# UPCNSL-ABS-FLS-ARD_v1_2.net
KiCad netlist of a schematic drawn in Altium Designer
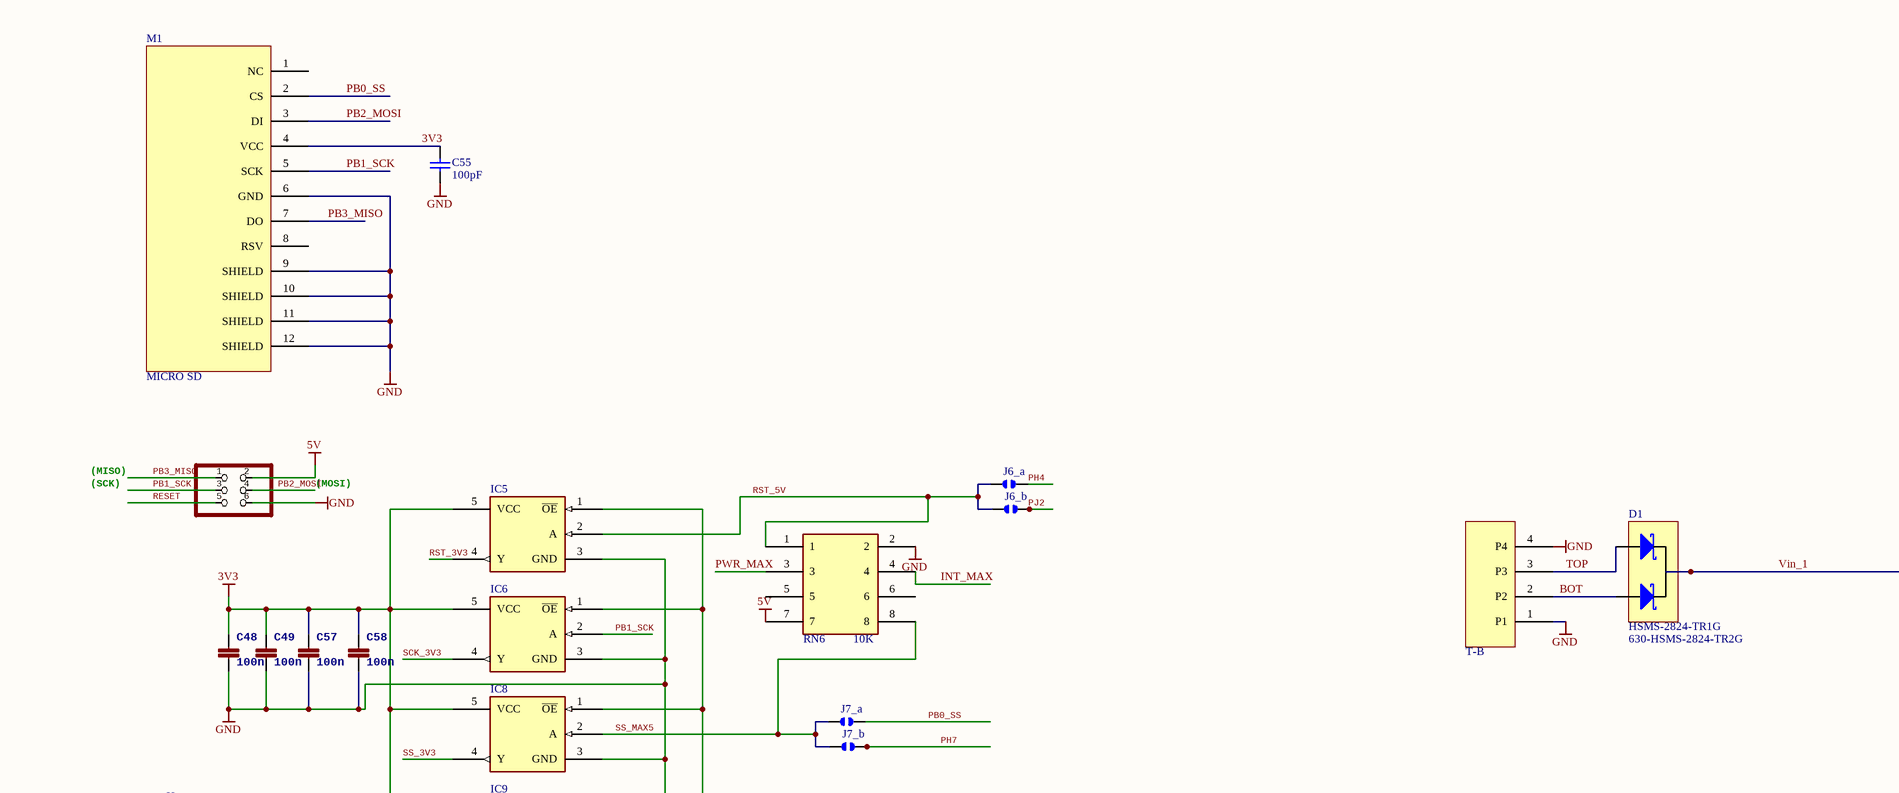
[diagram p0: UPCNSL-ABS-FLS-ARD_v1.2.SchDoc, top left]
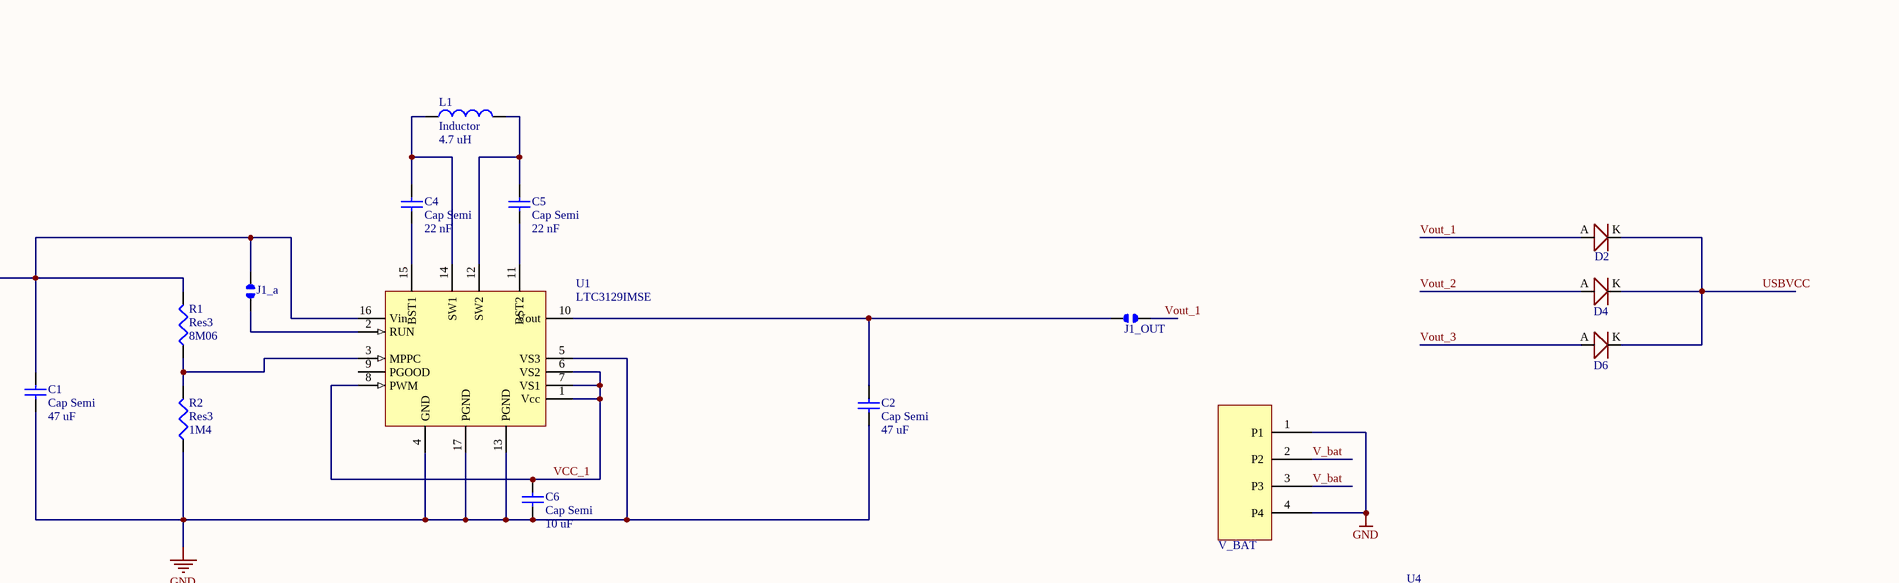
[diagram p1: UPCNSL-ABS-FLS-ARD_v1.2.SchDoc, top right]
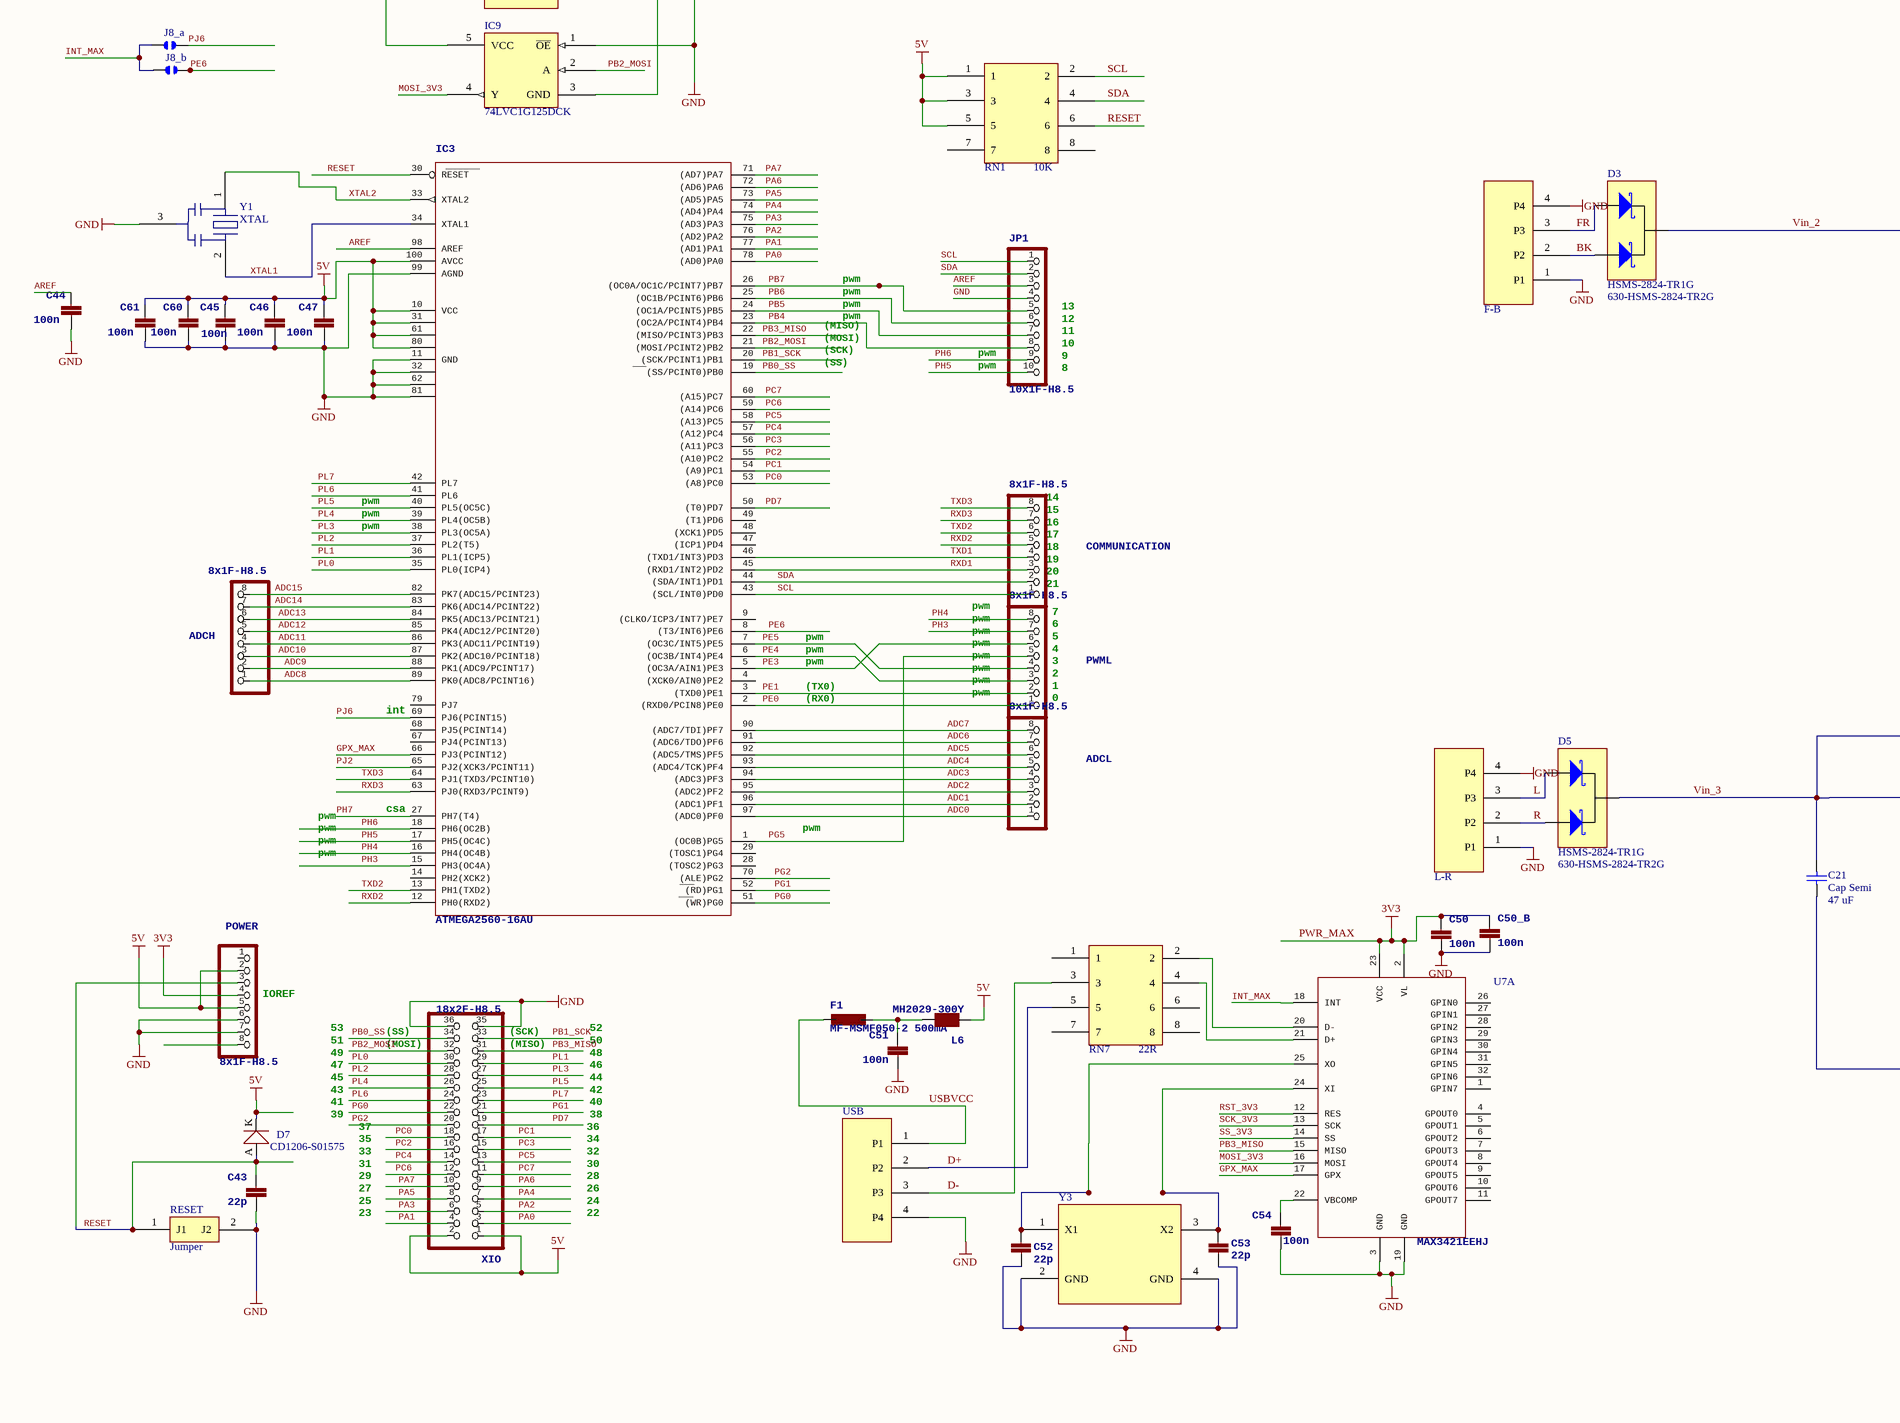
[diagram p2: UPCNSL-ABS-FLS-ARD_v1.2.SchDoc, bottom left]
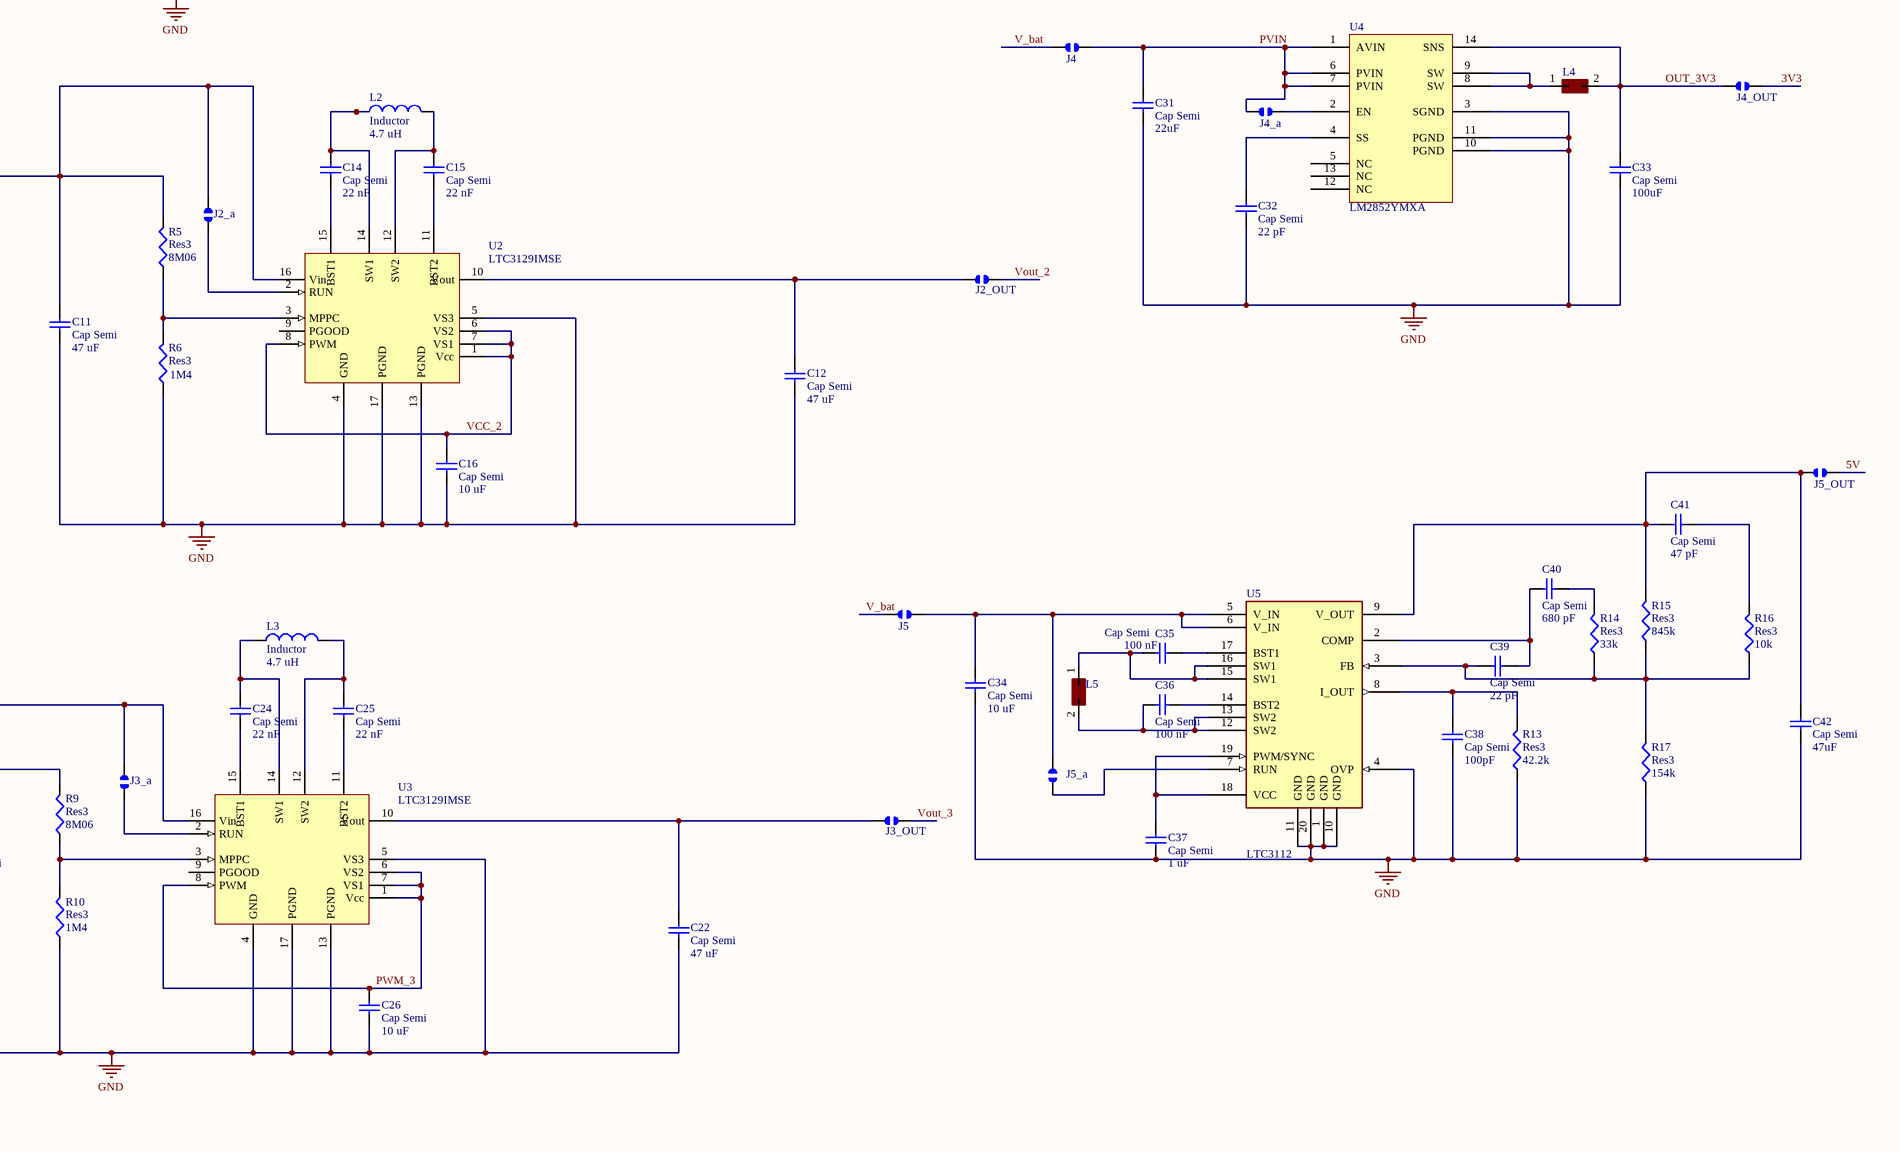
[diagram p3: UPCNSL-ABS-FLS-ARD_v1.2.SchDoc, bottom right]

(export (version "E")
  (design (tool "Eeschema 10.0.6"))
  (components
    (comp (ref "ADCH")
      (value "8x1F-H8.5")
      (footprint "ADCH")
      (description "<b>PIN HEADER</b>")
      (libsource (lib "SmartPrj") (part "PINHD-1X8"))
    )
    (comp (ref "ADCL")
      (value "8x1F-H8.5")
      (footprint "ADCL")
      (description "<b>PIN HEADER</b>")
      (libsource (lib "SmartPrj") (part "PINHD-1X8"))
    )
    (comp (ref "C1")
      (value "Cap Semi")
      (footprint "C1206")
      (description "Capacitor (Semiconductor SIM Model)")
      (fields (field (name "ALTIUM_VALUE") "47 uF") (field (name "PUBLISHER") "Altium Limited"))
      (libsource (lib "Miscellaneous Devices") (part "Cap Semi"))
    )
    (comp (ref "C2")
      (value "Cap Semi")
      (footprint "C1206")
      (description "Capacitor (Semiconductor SIM Model)")
      (fields (field (name "ALTIUM_VALUE") "47 uF") (field (name "PUBLISHER") "Altium Limited"))
      (libsource (lib "Miscellaneous Devices") (part "Cap Semi"))
    )
    (comp (ref "C4")
      (value "Cap Semi")
      (footprint "CAP0603")
      (description "Capacitor (Semiconductor SIM Model)")
      (fields (field (name "ALTIUM_VALUE") "22 nF") (field (name "PUBLISHER") "Altium Limited"))
      (libsource (lib "Miscellaneous Devices") (part "Cap Semi"))
    )
    (comp (ref "C5")
      (value "Cap Semi")
      (footprint "CAP0603")
      (description "Capacitor (Semiconductor SIM Model)")
      (fields (field (name "ALTIUM_VALUE") "22 nF") (field (name "PUBLISHER") "Altium Limited"))
      (libsource (lib "Miscellaneous Devices") (part "Cap Semi"))
    )
    (comp (ref "C6")
      (value "Cap Semi")
      (footprint "CAP0603")
      (description "Capacitor (Semiconductor SIM Model)")
      (fields (field (name "ALTIUM_VALUE") "10 uF") (field (name "PUBLISHER") "Altium Limited"))
      (libsource (lib "Miscellaneous Devices") (part "Cap Semi"))
    )
    (comp (ref "C11")
      (value "Cap Semi")
      (footprint "C1206")
      (description "Capacitor (Semiconductor SIM Model)")
      (fields (field (name "ALTIUM_VALUE") "47 uF") (field (name "PUBLISHER") "Altium Limited"))
      (libsource (lib "Miscellaneous Devices") (part "Cap Semi"))
    )
    (comp (ref "C12")
      (value "Cap Semi")
      (footprint "C1206")
      (description "Capacitor (Semiconductor SIM Model)")
      (fields (field (name "ALTIUM_VALUE") "47 uF") (field (name "PUBLISHER") "Altium Limited"))
      (libsource (lib "Miscellaneous Devices") (part "Cap Semi"))
    )
    (comp (ref "C14")
      (value "Cap Semi")
      (footprint "CAP0603")
      (description "Capacitor (Semiconductor SIM Model)")
      (fields (field (name "ALTIUM_VALUE") "22 nF") (field (name "PUBLISHER") "Altium Limited"))
      (libsource (lib "Miscellaneous Devices") (part "Cap Semi"))
    )
    (comp (ref "C15")
      (value "Cap Semi")
      (footprint "CAP0603")
      (description "Capacitor (Semiconductor SIM Model)")
      (fields (field (name "ALTIUM_VALUE") "22 nF") (field (name "PUBLISHER") "Altium Limited"))
      (libsource (lib "Miscellaneous Devices") (part "Cap Semi"))
    )
    (comp (ref "C16")
      (value "Cap Semi")
      (footprint "CAP0603")
      (description "Capacitor (Semiconductor SIM Model)")
      (fields (field (name "ALTIUM_VALUE") "10 uF") (field (name "PUBLISHER") "Altium Limited"))
      (libsource (lib "Miscellaneous Devices") (part "Cap Semi"))
    )
    (comp (ref "C21")
      (value "Cap Semi")
      (footprint "C1206")
      (description "Capacitor (Semiconductor SIM Model)")
      (fields (field (name "ALTIUM_VALUE") "47 uF") (field (name "PUBLISHER") "Altium Limited"))
      (libsource (lib "Miscellaneous Devices") (part "Cap Semi"))
    )
    (comp (ref "C22")
      (value "Cap Semi")
      (footprint "C1206")
      (description "Capacitor (Semiconductor SIM Model)")
      (fields (field (name "ALTIUM_VALUE") "47 uF") (field (name "PUBLISHER") "Altium Limited"))
      (libsource (lib "Miscellaneous Devices") (part "Cap Semi"))
    )
    (comp (ref "C24")
      (value "Cap Semi")
      (footprint "CAP0603")
      (description "Capacitor (Semiconductor SIM Model)")
      (fields (field (name "ALTIUM_VALUE") "22 nF") (field (name "PUBLISHER") "Altium Limited"))
      (libsource (lib "Miscellaneous Devices") (part "Cap Semi"))
    )
    (comp (ref "C25")
      (value "Cap Semi")
      (footprint "CAP0603")
      (description "Capacitor (Semiconductor SIM Model)")
      (fields (field (name "ALTIUM_VALUE") "22 nF") (field (name "PUBLISHER") "Altium Limited"))
      (libsource (lib "Miscellaneous Devices") (part "Cap Semi"))
    )
    (comp (ref "C26")
      (value "Cap Semi")
      (footprint "CAP0603")
      (description "Capacitor (Semiconductor SIM Model)")
      (fields (field (name "ALTIUM_VALUE") "10 uF") (field (name "PUBLISHER") "Altium Limited"))
      (libsource (lib "Miscellaneous Devices") (part "Cap Semi"))
    )
    (comp (ref "C31")
      (value "Cap Semi")
      (footprint "C1206")
      (description "Capacitor (Semiconductor SIM Model)")
      (fields (field (name "ALTIUM_VALUE") "22uF") (field (name "PUBLISHER") "Altium Limited"))
      (libsource (lib "Miscellaneous Devices") (part "Cap Semi"))
    )
    (comp (ref "C32")
      (value "Cap Semi")
      (footprint "CAP0603")
      (description "Capacitor (Semiconductor SIM Model)")
      (fields (field (name "ALTIUM_VALUE") "22 pF") (field (name "PUBLISHER") "Altium Limited"))
      (libsource (lib "Miscellaneous Devices") (part "Cap Semi"))
    )
    (comp (ref "C33")
      (value "Cap Semi")
      (footprint "C0805")
      (description "Capacitor (Semiconductor SIM Model)")
      (fields (field (name "ALTIUM_VALUE") "100uF") (field (name "PUBLISHER") "Altium Limited"))
      (libsource (lib "Miscellaneous Devices") (part "Cap Semi"))
    )
    (comp (ref "C34")
      (value "Cap Semi")
      (footprint "CAP0603")
      (description "Capacitor (Semiconductor SIM Model)")
      (fields (field (name "ALTIUM_VALUE") "10 uF") (field (name "PUBLISHER") "Altium Limited"))
      (libsource (lib "Miscellaneous Devices") (part "Cap Semi"))
    )
    (comp (ref "C35")
      (value "Cap Semi")
      (footprint "CAP0603")
      (description "Capacitor (Semiconductor SIM Model)")
      (fields (field (name "ALTIUM_VALUE") "100 nF") (field (name "PUBLISHER") "Altium Limited"))
      (libsource (lib "Miscellaneous Devices") (part "Cap Semi"))
    )
    (comp (ref "C36")
      (value "Cap Semi")
      (footprint "CAP0603")
      (description "Capacitor (Semiconductor SIM Model)")
      (fields (field (name "ALTIUM_VALUE") "100 nF") (field (name "PUBLISHER") "Altium Limited"))
      (libsource (lib "Miscellaneous Devices") (part "Cap Semi"))
    )
    (comp (ref "C37")
      (value "Cap Semi")
      (footprint "CAP0603")
      (description "Capacitor (Semiconductor SIM Model)")
      (fields (field (name "ALTIUM_VALUE") "1 uF") (field (name "PUBLISHER") "Altium Limited"))
      (libsource (lib "Miscellaneous Devices") (part "Cap Semi"))
    )
    (comp (ref "C38")
      (value "Cap Semi")
      (footprint "CAP0603")
      (description "Capacitor (Semiconductor SIM Model)")
      (fields (field (name "ALTIUM_VALUE") "100pF") (field (name "PUBLISHER") "Altium Limited"))
      (libsource (lib "Miscellaneous Devices") (part "Cap Semi"))
    )
    (comp (ref "C39")
      (value "Cap Semi")
      (footprint "CAP0603")
      (description "Capacitor (Semiconductor SIM Model)")
      (fields (field (name "ALTIUM_VALUE") "22 pF") (field (name "PUBLISHER") "Altium Limited"))
      (libsource (lib "Miscellaneous Devices") (part "Cap Semi"))
    )
    (comp (ref "C40")
      (value "Cap Semi")
      (footprint "CAP0603")
      (description "Capacitor (Semiconductor SIM Model)")
      (fields (field (name "ALTIUM_VALUE") "680 pF") (field (name "PUBLISHER") "Altium Limited"))
      (libsource (lib "Miscellaneous Devices") (part "Cap Semi"))
    )
    (comp (ref "C41")
      (value "Cap Semi")
      (footprint "CAP0603")
      (description "Capacitor (Semiconductor SIM Model)")
      (fields (field (name "ALTIUM_VALUE") "47 pF") (field (name "PUBLISHER") "Altium Limited"))
      (libsource (lib "Miscellaneous Devices") (part "Cap Semi"))
    )
    (comp (ref "C42")
      (value "Cap Semi")
      (footprint "C1206")
      (description "Capacitor (Semiconductor SIM Model)")
      (fields (field (name "ALTIUM_VALUE") "47uF") (field (name "PUBLISHER") "Altium Limited"))
      (libsource (lib "Miscellaneous Devices") (part "Cap Semi"))
    )
    (comp (ref "C43")
      (value "22p")
      (footprint "CAP0603")
      (description "<B>CAPACITOR</B>, European symbol")
      (fields (field (name ">NAME") "C43") (field (name ">VALUE") "22p"))
      (libsource (lib "SmartPrj") (part "C-EU0603-RND"))
    )
    (comp (ref "C44")
      (value "100n")
      (footprint "CAP0603")
      (description "<B>CAPACITOR</B>, European symbol")
      (libsource (lib "SmartPrj") (part "C-EU0603-RND"))
    )
    (comp (ref "C45")
      (value "100n")
      (footprint "CAP0603")
      (description "<B>CAPACITOR</B>, European symbol")
      (libsource (lib "SmartPrj") (part "C-EU0603-RND"))
    )
    (comp (ref "C46")
      (value "100n")
      (footprint "CAP0603")
      (description "<B>CAPACITOR</B>, European symbol")
      (libsource (lib "SmartPrj") (part "C-EU0603-RND"))
    )
    (comp (ref "C47")
      (value "100n")
      (footprint "CAP0603")
      (description "<B>CAPACITOR</B>, European symbol")
      (libsource (lib "SmartPrj") (part "C-EU0603-RND"))
    )
    (comp (ref "C48")
      (value "100n")
      (footprint "CAP0603")
      (description "<B>CAPACITOR</B>, European symbol")
      (fields (field (name ">NAME") "C48") (field (name ">VALUE") "100n"))
      (libsource (lib "") (part "C-EU0603-RND_1"))
    )
    (comp (ref "C49")
      (value "100n")
      (footprint "CAP0603")
      (description "<B>CAPACITOR</B>, European symbol")
      (fields (field (name ">NAME") "C49") (field (name ">VALUE") "100n"))
      (libsource (lib "") (part "C-EU0603-RND_1"))
    )
    (comp (ref "C50")
      (value "100n")
      (footprint "CAP0603")
      (description "<B>CAPACITOR</B>, European symbol")
      (fields (field (name ">NAME") "C50") (field (name ">VALUE") "100n"))
      (libsource (lib "") (part "C-EU0603-RND_1"))
    )
    (comp (ref "C50_B")
      (value "100n")
      (footprint "CAP0603")
      (description "<B>CAPACITOR</B>, European symbol")
      (fields (field (name ">NAME") "C50_B") (field (name ">VALUE") "100n"))
      (libsource (lib "") (part "C-EU0603-RND_1"))
    )
    (comp (ref "C51")
      (value "100n")
      (footprint "CAP0603")
      (description "<B>CAPACITOR</B>, European symbol")
      (fields (field (name ">NAME") "C51") (field (name ">VALUE") "100n"))
      (libsource (lib "SmartPrj") (part "C-EU0603-RND"))
    )
    (comp (ref "C52")
      (value "22p")
      (footprint "CAP0603")
      (description "<B>CAPACITOR</B>, European symbol")
      (libsource (lib "") (part "C-EU0603-RND_2"))
    )
    (comp (ref "C53")
      (value "22p")
      (footprint "CAP0603")
      (description "<B>CAPACITOR</B>, European symbol")
      (libsource (lib "") (part "C-EU0603-RND_2"))
    )
    (comp (ref "C54")
      (value "100n")
      (footprint "CAP0603")
      (description "<B>CAPACITOR</B>, European symbol")
      (fields (field (name ">NAME") "C54") (field (name ">VALUE") "100n"))
      (libsource (lib "SmartPrj") (part "C-EU0603-RND"))
    )
    (comp (ref "C55")
      (value "100pF")
      (footprint "CAP0603")
      (description "Capacitor")
      (fields (field (name "Comment") "CAP0603"))
      (libsource (lib "UPCNSL-ABS-FLS-ARD_v1") (part "CAP0603"))
    )
    (comp (ref "C57")
      (value "100n")
      (footprint "CAP0603")
      (description "<B>CAPACITOR</B>, European symbol")
      (fields (field (name ">NAME") "C57") (field (name ">VALUE") "100n"))
      (libsource (lib "") (part "C-EU0603-RND_1"))
    )
    (comp (ref "C58")
      (value "100n")
      (footprint "CAP0603")
      (description "<B>CAPACITOR</B>, European symbol")
      (fields (field (name ">NAME") "C58") (field (name ">VALUE") "100n"))
      (libsource (lib "") (part "C-EU0603-RND_1"))
    )
    (comp (ref "C60")
      (value "100n")
      (footprint "CAP0603")
      (description "<B>CAPACITOR</B>, European symbol")
      (libsource (lib "SmartPrj") (part "C-EU0603-RND"))
    )
    (comp (ref "C61")
      (value "100n")
      (footprint "CAP0603")
      (description "<B>CAPACITOR</B>, European symbol")
      (libsource (lib "SmartPrj") (part "C-EU0603-RND"))
    )
    (comp (ref "COMMUNICATION")
      (value "8x1F-H8.5")
      (footprint "COMMUNICATION")
      (description "<b>PIN HEADER</b>")
      (libsource (lib "SmartPrj") (part "PINHD-1X8"))
    )
    (comp (ref "D1")
      (value "HSMS-2824-TR1G")
      (footprint "SOT23-3")
      (description "DIODE, RF, SCHOTTKY, DUAL, SOT-23")
      (fields (field (name "SUPPLIER PART NUMBER 1") "630-HSMS-2824-TR2G"))
      (libsource (lib "Arduino_Space") (part "HSMS-2824-TR1G"))
    )
    (comp (ref "D2")
      (value "DIODE")
      (footprint "(Schottky diode) SODFL160X70-2N")
      (libsource (lib "UPCNSL-ABS-FLS-ARD") (part "DIODE"))
    )
    (comp (ref "D3")
      (value "HSMS-2824-TR1G")
      (footprint "SOT23-3")
      (description "DIODE, RF, SCHOTTKY, DUAL, SOT-23")
      (fields (field (name "SUPPLIER PART NUMBER 1") "630-HSMS-2824-TR2G"))
      (libsource (lib "Arduino_Space") (part "HSMS-2824-TR1G"))
    )
    (comp (ref "D4")
      (value "DIODE")
      (footprint "(Schottky diode) SODFL160X70-2N")
      (libsource (lib "UPCNSL-ABS-FLS-ARD") (part "DIODE"))
    )
    (comp (ref "D5")
      (value "HSMS-2824-TR1G")
      (footprint "SOT23-3")
      (description "DIODE, RF, SCHOTTKY, DUAL, SOT-23")
      (fields (field (name "SUPPLIER PART NUMBER 1") "630-HSMS-2824-TR2G"))
      (libsource (lib "Arduino_Space") (part "HSMS-2824-TR1G"))
    )
    (comp (ref "D6")
      (value "DIODE")
      (footprint "(Schottky diode) SODFL160X70-2N")
      (libsource (lib "UPCNSL-ABS-FLS-ARD") (part "DIODE"))
    )
    (comp (ref "D7")
      (value "CD1206-S01575")
      (footprint "SMD DIODE")
      (libsource (lib "Arduino_Space") (part "DIODE"))
    )
    (comp (ref "F-B")
      (value "HEADER_CONNECTION")
      (footprint "HEADER_CONNECTION")
      (description "Front and Back connections")
      (libsource (lib "") (part "HEADER_CONNECTION_1"))
    )
    (comp (ref "F2")
      (value "MF-MSMF050-2 500mA")
      (footprint "FUSE")
      (description "<B>INDUCTOR</B>, European symbol")
      (fields (field (name ">NAME") "F1") (field (name ">VALUE") "MF-MSMF050-2 500mA"))
      (libsource (lib "rcl") (part "L-EUL1812"))
    )
    (comp (ref "IC3")
      (value "ATMEGA2560-16AU")
      (footprint "TSQFP50P1600X1600X120-100N")
      (libsource (lib "SmartPrj") (part "ATMEGA2560AU"))
    )
    (comp (ref "IC5")
      (value "74LVC1G125DCK")
      (footprint "SOT65P210X110-5N")
      (libsource (lib "Arduino_Space") (part "74LVC1G125DCK"))
    )
    (comp (ref "IC6")
      (value "74LVC1G125DCK")
      (footprint "SOT65P210X110-5N")
      (libsource (lib "Arduino_Space") (part "74LVC1G125DCK"))
    )
    (comp (ref "IC8")
      (value "74LVC1G125DCK")
      (footprint "SOT65P210X110-5N")
      (libsource (lib "Arduino_Space") (part "74LVC1G125DCK"))
    )
    (comp (ref "IC9")
      (value "74LVC1G125DCK")
      (footprint "SOT65P210X110-5N")
      (libsource (lib "Arduino_Space") (part "74LVC1G125DCK"))
    )
    (comp (ref "ICSP")
      (value "3x2M")
      (footprint "Header 3x2")
      (description "<b>PIN HEADER</b>")
      (libsource (lib "SmartPrj") (part "PINHD-2X3"))
    )
    (comp (ref "J1_a")
      (value "Jumper_Solderpad")
      (footprint "JUMPER_SOLDERPAD")
      (libsource (lib "UPCNSL-ABS-FLS-ARD_v1") (part "Jumper_Solderpad"))
    )
    (comp (ref "J1_OUT")
      (value "Jumper_Solderpad")
      (footprint "JUMPER_SOLDERPAD")
      (libsource (lib "UPCNSL-ABS-FLS-ARD") (part "Jumper_Solderpad"))
    )
    (comp (ref "J2_a")
      (value "Jumper_Solderpad")
      (footprint "JUMPER_SOLDERPAD")
      (libsource (lib "UPCNSL-ABS-FLS-ARD_v1") (part "Jumper_Solderpad"))
    )
    (comp (ref "J2_OUT")
      (value "Jumper_Solderpad")
      (footprint "JUMPER_SOLDERPAD")
      (libsource (lib "UPCNSL-ABS-FLS-ARD") (part "Jumper_Solderpad"))
    )
    (comp (ref "J3_a")
      (value "Jumper_Solderpad")
      (footprint "JUMPER_SOLDERPAD")
      (libsource (lib "UPCNSL-ABS-FLS-ARD_v1") (part "Jumper_Solderpad"))
    )
    (comp (ref "J3_OUT")
      (value "Jumper_Solderpad")
      (footprint "JUMPER_SOLDERPAD")
      (libsource (lib "UPCNSL-ABS-FLS-ARD") (part "Jumper_Solderpad"))
    )
    (comp (ref "J4")
      (value "Jumper_Solderpad")
      (footprint "JUMPER_SOLDERPAD")
      (libsource (lib "UPCNSL-ABS-FLS-ARD") (part "Jumper_Solderpad"))
    )
    (comp (ref "J4_a")
      (value "Jumper_Solderpad")
      (footprint "JUMPER_SOLDERPAD")
      (libsource (lib "UPCNSL-ABS-FLS-ARD") (part "Jumper_Solderpad"))
    )
    (comp (ref "J4_OUT")
      (value "Jumper_Solderpad")
      (footprint "JUMPER_SOLDERPAD")
      (libsource (lib "UPCNSL-ABS-FLS-ARD") (part "Jumper_Solderpad"))
    )
    (comp (ref "J5")
      (value "Jumper_Solderpad")
      (footprint "JUMPER_SOLDERPAD")
      (libsource (lib "UPCNSL-ABS-FLS-ARD") (part "Jumper_Solderpad"))
    )
    (comp (ref "J5_a")
      (value "Jumper_Solderpad")
      (footprint "JUMPER_SOLDERPAD")
      (libsource (lib "") (part "Jumper_Solderpad_1"))
    )
    (comp (ref "J5_OUT")
      (value "Jumper_Solderpad")
      (footprint "JUMPER_SOLDERPAD")
      (libsource (lib "UPCNSL-ABS-FLS-ARD") (part "Jumper_Solderpad"))
    )
    (comp (ref "J6_a")
      (value "Jumper_Solderpad")
      (footprint "JUMPER_SOLDERPAD")
      (libsource (lib "EPS") (part "Jumper_Solderpad"))
    )
    (comp (ref "J6_b")
      (value "Jumper_Solderpad")
      (footprint "JUMPER_SOLDERPAD")
      (libsource (lib "EPS") (part "Jumper_Solderpad"))
    )
    (comp (ref "J7_a")
      (value "Jumper_Solderpad")
      (footprint "JUMPER_SOLDERPAD")
      (libsource (lib "EPS") (part "Jumper_Solderpad"))
    )
    (comp (ref "J7_b")
      (value "Jumper_Solderpad")
      (footprint "JUMPER_SOLDERPAD")
      (libsource (lib "EPS") (part "Jumper_Solderpad"))
    )
    (comp (ref "J8_a")
      (value "Jumper_Solderpad")
      (footprint "JUMPER_SOLDERPAD")
      (libsource (lib "EPS") (part "Jumper_Solderpad"))
    )
    (comp (ref "J8_b")
      (value "Jumper_Solderpad")
      (footprint "JUMPER_SOLDERPAD")
      (libsource (lib "EPS") (part "Jumper_Solderpad"))
    )
    (comp (ref "JP1")
      (value "10x1F-H8.5")
      (footprint "HEADER 1X10")
      (description "<b>PIN HEADER</b>")
      (fields (field (name ">NAME") "JP1") (field (name ">VALUE") "10x1F-H8.5"))
      (libsource (lib "SmartPrj") (part "PINHD-1X10"))
    )
    (comp (ref "L-R")
      (value "HEADER_CONNECTION")
      (footprint "HEADER_CONNECTION")
      (description "Left and Right connections")
      (libsource (lib "") (part "HEADER_CONNECTION_1"))
    )
    (comp (ref "L1")
      (value "Inductor")
      (footprint "CAP0603")
      (fields (field (name "ALTIUM_VALUE") "4.7 uH") (field (name "PUBLISHER") "Altium Limited"))
      (libsource (lib "Miscellaneous Devices") (part "Inductor"))
    )
    (comp (ref "L2")
      (value "Inductor")
      (footprint "CAP0603")
      (fields (field (name "ALTIUM_VALUE") "4.7 uH") (field (name "PUBLISHER") "Altium Limited"))
      (libsource (lib "Miscellaneous Devices") (part "Inductor"))
    )
    (comp (ref "L3")
      (value "Inductor")
      (footprint "CAP0603")
      (fields (field (name "ALTIUM_VALUE") "4.7 uH") (field (name "PUBLISHER") "Altium Limited"))
      (libsource (lib "Miscellaneous Devices") (part "Inductor"))
    )
    (comp (ref "L4")
      (value "INDUCTOR")
      (footprint "INDUCTOR - 74405215")
      (libsource (lib "") (part "INDUCTOR_1"))
    )
    (comp (ref "L5")
      (value "INDUCTOR")
      (footprint "INDUCTOR - 1008[2520]")
      (libsource (lib "UPCNSL-ABS-FLS-ARD_v1") (part "INDUCTOR"))
    )
    (comp (ref "L7")
      (value "MH2029-300Y")
      (footprint "INDUCTOR")
      (fields (field (name ">VALUE") "MH2029-300Y") (field (name ">NAME") "L6"))
      (libsource (lib "wuerth-elektronik") (part "WE-CBF_0805"))
    )
    (comp (ref "M1")
      (value "MICRO SD")
      (footprint "Micro SD holder")
      (libsource (lib "UPCNSL-ABS-FLS-ARD_v1") (part "MICRO SD"))
    )
    (comp (ref "POWER")
      (value "8x1F-H8.5")
      (footprint "POWER")
      (description "<b>PIN HEADER</b>")
      (libsource (lib "SmartPrj") (part "PINHD-1X8"))
    )
    (comp (ref "PWML")
      (value "8x1F-H8.5")
      (footprint "PWM")
      (description "<b>PIN HEADER</b>")
      (libsource (lib "SmartPrj") (part "PINHD-1X8"))
    )
    (comp (ref "R1")
      (value "Res3")
      (footprint "J1-0603")
      (description "Resistor")
      (fields (field (name "ALTIUM_VALUE") "8M06") (field (name "PUBLISHER") "Altium Limited"))
      (libsource (lib "Miscellaneous Devices") (part "Res3"))
    )
    (comp (ref "R2")
      (value "Res3")
      (footprint "J1-0603")
      (description "Resistor")
      (fields (field (name "ALTIUM_VALUE") "1M4") (field (name "PUBLISHER") "Altium Limited"))
      (libsource (lib "Miscellaneous Devices") (part "Res3"))
    )
    (comp (ref "R5")
      (value "Res3")
      (footprint "J1-0603")
      (description "Resistor")
      (fields (field (name "ALTIUM_VALUE") "8M06") (field (name "PUBLISHER") "Altium Limited"))
      (libsource (lib "Miscellaneous Devices") (part "Res3"))
    )
    (comp (ref "R6")
      (value "Res3")
      (footprint "J1-0603")
      (description "Resistor")
      (fields (field (name "ALTIUM_VALUE") "1M4") (field (name "PUBLISHER") "Altium Limited"))
      (libsource (lib "Miscellaneous Devices") (part "Res3"))
    )
    (comp (ref "R9")
      (value "Res3")
      (footprint "J1-0603")
      (description "Resistor")
      (fields (field (name "ALTIUM_VALUE") "8M06") (field (name "PUBLISHER") "Altium Limited"))
      (libsource (lib "Miscellaneous Devices") (part "Res3"))
    )
    (comp (ref "R10")
      (value "Res3")
      (footprint "J1-0603")
      (description "Resistor")
      (fields (field (name "ALTIUM_VALUE") "1M4") (field (name "PUBLISHER") "Altium Limited"))
      (libsource (lib "Miscellaneous Devices") (part "Res3"))
    )
    (comp (ref "R13")
      (value "Res3")
      (footprint "J1-0603")
      (description "Resistor")
      (fields (field (name "ALTIUM_VALUE") "42.2k") (field (name "PUBLISHER") "Altium Limited"))
      (libsource (lib "Miscellaneous Devices") (part "Res3"))
    )
    (comp (ref "R14")
      (value "Res3")
      (footprint "J1-0603")
      (description "Resistor")
      (fields (field (name "ALTIUM_VALUE") "33k") (field (name "PUBLISHER") "Altium Limited"))
      (libsource (lib "Miscellaneous Devices") (part "Res3"))
    )
    (comp (ref "R15")
      (value "Res3")
      (footprint "J1-0603")
      (description "Resistor")
      (fields (field (name "ALTIUM_VALUE") "845k") (field (name "PUBLISHER") "Altium Limited"))
      (libsource (lib "Miscellaneous Devices") (part "Res3"))
    )
    (comp (ref "R16")
      (value "Res3")
      (footprint "J1-0603")
      (description "Resistor")
      (fields (field (name "ALTIUM_VALUE") "10k") (field (name "PUBLISHER") "Altium Limited"))
      (libsource (lib "Miscellaneous Devices") (part "Res3"))
    )
    (comp (ref "R17")
      (value "Res3")
      (footprint "J1-0603")
      (description "Resistor")
      (fields (field (name "ALTIUM_VALUE") "154k") (field (name "PUBLISHER") "Altium Limited"))
      (libsource (lib "Miscellaneous Devices") (part "Res3"))
    )
    (comp (ref "RESET")
      (value "Jumper")
      (footprint "Jumper")
      (libsource (lib "UPCNSL-ABS-FLS-ARD_v1.2") (part "Jumper"))
    )
    (comp (ref "RN1")
      (value "10K")
      (footprint "CAF-80P319X159-8N")
      (libsource (lib "Arduino_Space") (part "RES_ARRAY"))
    )
    (comp (ref "RN6")
      (value "10K")
      (footprint "CAF-80P319X159-8N")
      (libsource (lib "Arduino_Space") (part "RES_ARRAY"))
    )
    (comp (ref "RN7")
      (value "22R")
      (footprint "CAF-80P319X159-8N")
      (libsource (lib "Arduino_Space") (part "RES_ARRAY"))
    )
    (comp (ref "T-B")
      (value "HEADER_CONNECTION")
      (footprint "HEADER_CONNECTION")
      (description "Top and Bottom connections")
      (libsource (lib "") (part "HEADER_CONNECTION_1"))
    )
    (comp (ref "U1")
      (value "LTC3129IMSE")
      (footprint "MSOP-16")
      (description "15V, 200mA Synchronous Buck-Boost DC/DC Converter with 1.3µA Quiescent Current")
      (libsource (lib "UPCNSL-ABS-FLS-ARD_v1.2") (part "LTC3129"))
    )
    (comp (ref "U2")
      (value "LTC3129IMSE")
      (footprint "MSOP-16")
      (description "15V, 200mA Synchronous Buck-Boost DC/DC Converter with 1.3µA Quiescent Current")
      (libsource (lib "UPCNSL-ABS-FLS-ARD_v1.2") (part "LTC3129"))
    )
    (comp (ref "U3")
      (value "LTC3129IMSE")
      (footprint "MSOP-16")
      (description "15V, 200mA Synchronous Buck-Boost DC/DC Converter with 1.3µA Quiescent Current")
      (libsource (lib "UPCNSL-ABS-FLS-ARD_v1.2") (part "LTC3129"))
    )
    (comp (ref "U4")
      (value "LM2852YMXA")
      (footprint "TSOP65P650X110-14N (LM2852YMXA)")
      (libsource (lib "Arduino_Space") (part "LM2852YMXA"))
    )
    (comp (ref "U5")
      (value "LTC3112")
      (footprint "SSOP-SS20")
      (description "IC REG BUCK BOOST ADJ 2.5A 16DFN")
      (libsource (lib "UPCNSL-ABS-FLS-ARD") (part "LTC3112EDHD#PBF"))
    )
    (comp (ref "U7A")
      (value "MAX3421EEHJ")
      (footprint "TSQFP50P700X700X120-32N")
      (description "MAX3421 SPI to USB Interface Chip")
      (libsource (lib "bibaja") (part "MAX3421EEHJ"))
    )
    (comp (ref "USB")
      (value "HEADER_CONNECTION")
      (footprint "HEADER_CONNECTION")
      (libsource (lib "UPCNSL-ABS-FLS-ARD_v1") (part "HEADER_CONNECTION"))
    )
    (comp (ref "V_BAT")
      (value "HEADER_CONNECTION")
      (footprint "HEADER_CONNECTION")
      (libsource (lib "UPCNSL-ABS-FLS-ARD_v1") (part "HEADER_CONNECTION"))
    )
    (comp (ref "XIO")
      (value "18x2F-H8.5")
      (footprint "HEADER 2X18")
      (description "<b>PIN HEADER</b>")
      (fields (field (name ">NAME") "XIO") (field (name ">VALUE") "18x2F-H8.5"))
      (libsource (lib "SmartPrj") (part "PINHD-2X18"))
    )
    (comp (ref "Y1")
      (value "XTAL")
      (footprint "RESONATOR 3 PINS")
      (libsource (lib "UPCNSL-ABS-FLS-ARD") (part "RESONATOR 16MHz"))
    )
    (comp (ref "Y3")
      (value "Crystal")
      (footprint "CRYSTAL")
      (libsource (lib "UPCNSL-ABS-FLS-ARD") (part "Crystal"))
    )
  )
  (nets
    (net (code "2") (name "/ADC0") (class "Default")
      (node (ref "ADCL") (pin "1") (pinfunction "1_1") (pintype "passive"))
      (node (ref "IC3") (pin "97") (pinfunction "(ADC0)PF0_97") (pintype "passive"))
    )
    (net (code "3") (name "/ADC1") (class "Default")
      (node (ref "ADCL") (pin "2") (pinfunction "2_2") (pintype "passive"))
      (node (ref "IC3") (pin "96") (pinfunction "(ADC1)PF1_96") (pintype "passive"))
    )
    (net (code "4") (name "/ADC2") (class "Default")
      (node (ref "ADCL") (pin "3") (pinfunction "3_3") (pintype "passive"))
      (node (ref "IC3") (pin "95") (pinfunction "(ADC2)PF2_95") (pintype "passive"))
    )
    (net (code "5") (name "/ADC3") (class "Default")
      (node (ref "ADCL") (pin "4") (pinfunction "4_4") (pintype "passive"))
      (node (ref "IC3") (pin "94") (pinfunction "(ADC3)PF3_94") (pintype "passive"))
    )
    (net (code "6") (name "/ADC4") (class "Default")
      (node (ref "ADCL") (pin "5") (pinfunction "5_5") (pintype "passive"))
      (node (ref "IC3") (pin "93") (pinfunction "(ADC4/TCK)PF4_93") (pintype "passive"))
    )
    (net (code "7") (name "/ADC5") (class "Default")
      (node (ref "ADCL") (pin "6") (pinfunction "6_6") (pintype "passive"))
      (node (ref "IC3") (pin "92") (pinfunction "(ADC5/TMS)PF5_92") (pintype "passive"))
    )
    (net (code "8") (name "/ADC6") (class "Default")
      (node (ref "ADCL") (pin "7") (pinfunction "7_7") (pintype "passive"))
      (node (ref "IC3") (pin "91") (pinfunction "(ADC6/TDO)PF6_91") (pintype "passive"))
    )
    (net (code "9") (name "/ADC7") (class "Default")
      (node (ref "ADCL") (pin "8") (pinfunction "8_8") (pintype "passive"))
      (node (ref "IC3") (pin "90") (pinfunction "(ADC7/TDI)PF7_90") (pintype "passive"))
    )
    (net (code "10") (name "/ADC8") (class "Default")
      (node (ref "ADCH") (pin "1") (pinfunction "1_1") (pintype "passive"))
      (node (ref "IC3") (pin "89") (pinfunction "PK0(ADC8/PCINT16)_89") (pintype "passive"))
    )
    (net (code "11") (name "/ADC9") (class "Default")
      (node (ref "ADCH") (pin "2") (pinfunction "2_2") (pintype "passive"))
      (node (ref "IC3") (pin "88") (pinfunction "PK1(ADC9/PCINT17)_88") (pintype "passive"))
    )
    (net (code "12") (name "/ADC10") (class "Default")
      (node (ref "ADCH") (pin "3") (pinfunction "3_3") (pintype "passive"))
      (node (ref "IC3") (pin "87") (pinfunction "PK2(ADC10/PCINT18)_87") (pintype "passive"))
    )
    (net (code "13") (name "/ADC11") (class "Default")
      (node (ref "ADCH") (pin "4") (pinfunction "4_4") (pintype "passive"))
      (node (ref "IC3") (pin "86") (pinfunction "PK3(ADC11/PCINT19)_86") (pintype "passive"))
    )
    (net (code "14") (name "/ADC12") (class "Default")
      (node (ref "ADCH") (pin "5") (pinfunction "5_5") (pintype "passive"))
      (node (ref "IC3") (pin "85") (pinfunction "PK4(ADC12/PCINT20)_85") (pintype "passive"))
    )
    (net (code "15") (name "/ADC13") (class "Default")
      (node (ref "ADCH") (pin "6") (pinfunction "6_6") (pintype "passive"))
      (node (ref "IC3") (pin "84") (pinfunction "PK5(ADC13/PCINT21)_84") (pintype "passive"))
    )
    (net (code "16") (name "/ADC14") (class "Default")
      (node (ref "ADCH") (pin "7") (pinfunction "7_7") (pintype "passive"))
      (node (ref "IC3") (pin "83") (pinfunction "PK6(ADC14/PCINT22)_83") (pintype "passive"))
    )
    (net (code "17") (name "/ADC15") (class "Default")
      (node (ref "ADCH") (pin "8") (pinfunction "8_8") (pintype "passive"))
      (node (ref "IC3") (pin "82") (pinfunction "PK7(ADC15/PCINT23)_82") (pintype "passive"))
    )
    (net (code "18") (name "/AREF") (class "Default")
      (node (ref "C44") (pin "1") (pinfunction "1_1") (pintype "passive"))
      (node (ref "IC3") (pin "98") (pinfunction "AREF_98") (pintype "passive"))
      (node (ref "JP1") (pin "3") (pinfunction "3_3") (pintype "passive"))
    )
    (net (code "19") (name "/BK") (class "Default")
      (node (ref "D3") (pin "2") (pinfunction "A2_2") (pintype "passive"))
      (node (ref "F-B") (pin "2") (pinfunction "P2_2") (pintype "passive"))
    )
    (net (code "20") (name "/BOT") (class "Default")
      (node (ref "D1") (pin "2") (pinfunction "A2_2") (pintype "passive"))
      (node (ref "T-B") (pin "2") (pinfunction "P2_2") (pintype "passive"))
    )
    (net (code "21") (name "/D+") (class "Default")
      (node (ref "RN7") (pin "5") (pinfunction "5_5") (pintype "passive"))
      (node (ref "USB") (pin "2") (pinfunction "P2_2") (pintype "passive"))
    )
    (net (code "22") (name "/D-") (class "Default")
      (node (ref "RN7") (pin "3") (pinfunction "3_3") (pintype "passive"))
      (node (ref "USB") (pin "3") (pinfunction "P3_3") (pintype "passive"))
    )
    (net (code "23") (name "/FR") (class "Default")
      (node (ref "D3") (pin "1") (pinfunction "A1_1") (pintype "passive"))
      (node (ref "F-B") (pin "3") (pinfunction "P3_3") (pintype "passive"))
    )
    (net (code "24") (name "/GPX_MAX") (class "Default")
      (node (ref "IC3") (pin "66") (pinfunction "PJ3(PCINT12)_66") (pintype "passive"))
      (node (ref "U7A") (pin "17") (pinfunction "GPX_17") (pintype "passive"))
    )
    (net (code "25") (name "/INT_MAX") (class "Default")
      (node (ref "J8_a") (pin "1") (pinfunction "1_1") (pintype "passive"))
      (node (ref "J8_b") (pin "1") (pinfunction "1_1") (pintype "passive"))
      (node (ref "RN6") (pin "4") (pinfunction "4_4") (pintype "passive"))
      (node (ref "U7A") (pin "18") (pinfunction "INT_18") (pintype "passive"))
    )
    (net (code "26") (name "/L") (class "Default")
      (node (ref "D5") (pin "1") (pinfunction "A1_1") (pintype "passive"))
      (node (ref "L-R") (pin "3") (pinfunction "P3_3") (pintype "passive"))
    )
    (net (code "27") (name "/MOSI_3V3") (class "Default")
      (node (ref "IC9") (pin "4") (pinfunction "Y_4") (pintype "output"))
      (node (ref "U7A") (pin "16") (pinfunction "MOSI_16") (pintype "passive"))
    )
    (net (code "28") (name "/OUT_3V3") (class "Default")
      (node (ref "C33") (pin "1") (pinfunction "1_1") (pintype "passive"))
      (node (ref "J4_OUT") (pin "1") (pinfunction "1_1") (pintype "passive"))
      (node (ref "L4") (pin "2") (pinfunction "2_2") (pintype "passive"))
      (node (ref "U4") (pin "14") (pinfunction "SNS_14") (pintype "passive"))
    )
    (net (code "29") (name "/PA0") (class "Default")
      (node (ref "IC3") (pin "78") (pinfunction "(AD0)PA0_78") (pintype "passive"))
      (node (ref "XIO") (pin "3") (pinfunction "3_3") (pintype "passive"))
    )
    (net (code "30") (name "/PA1") (class "Default")
      (node (ref "IC3") (pin "77") (pinfunction "(AD1)PA1_77") (pintype "passive"))
      (node (ref "XIO") (pin "4") (pinfunction "4_4") (pintype "passive"))
    )
    (net (code "31") (name "/PA2") (class "Default")
      (node (ref "IC3") (pin "76") (pinfunction "(AD2)PA2_76") (pintype "passive"))
      (node (ref "XIO") (pin "5") (pinfunction "5_5") (pintype "passive"))
    )
    (net (code "32") (name "/PA3") (class "Default")
      (node (ref "IC3") (pin "75") (pinfunction "(AD3)PA3_75") (pintype "passive"))
      (node (ref "XIO") (pin "6") (pinfunction "6_6") (pintype "passive"))
    )
    (net (code "33") (name "/PA4") (class "Default")
      (node (ref "IC3") (pin "74") (pinfunction "(AD4)PA4_74") (pintype "passive"))
      (node (ref "XIO") (pin "7") (pinfunction "7_7") (pintype "passive"))
    )
    (net (code "34") (name "/PA5") (class "Default")
      (node (ref "IC3") (pin "73") (pinfunction "(AD5)PA5_73") (pintype "passive"))
      (node (ref "XIO") (pin "8") (pinfunction "8_8") (pintype "passive"))
    )
    (net (code "35") (name "/PA6") (class "Default")
      (node (ref "IC3") (pin "72") (pinfunction "(AD6)PA6_72") (pintype "passive"))
      (node (ref "XIO") (pin "9") (pinfunction "9_9") (pintype "passive"))
    )
    (net (code "36") (name "/PA7") (class "Default")
      (node (ref "IC3") (pin "71") (pinfunction "(AD7)PA7_71") (pintype "passive"))
      (node (ref "XIO") (pin "10") (pinfunction "10_10") (pintype "passive"))
    )
    (net (code "37") (name "/PB0_SS") (class "Default")
      (node (ref "IC3") (pin "19") (pinfunction "(SS/PCINT0)PB0_19") (pintype "passive"))
      (node (ref "J7_a") (pin "2") (pinfunction "2_2") (pintype "passive"))
      (node (ref "M1") (pin "2") (pinfunction "CS_2") (pintype "passive"))
      (node (ref "XIO") (pin "34") (pinfunction "34_34") (pintype "passive"))
    )
    (net (code "38") (name "/PB1_SCK") (class "Default")
      (node (ref "IC3") (pin "20") (pinfunction "(SCK/PCINT1)PB1_20") (pintype "passive"))
      (node (ref "IC6") (pin "2") (pinfunction "A_2") (pintype "input"))
      (node (ref "ICSP") (pin "3") (pinfunction "3_3") (pintype "passive"))
      (node (ref "M1") (pin "5") (pinfunction "SCK_5") (pintype "passive"))
      (node (ref "XIO") (pin "33") (pinfunction "33_33") (pintype "passive"))
    )
    (net (code "39") (name "/PB2_MOSI") (class "Default")
      (node (ref "IC3") (pin "21") (pinfunction "(MOSI/PCINT2)PB2_21") (pintype "passive"))
      (node (ref "IC9") (pin "2") (pinfunction "A_2") (pintype "input"))
      (node (ref "ICSP") (pin "4") (pinfunction "4_4") (pintype "passive"))
      (node (ref "M1") (pin "3") (pinfunction "DI_3") (pintype "passive"))
      (node (ref "XIO") (pin "32") (pinfunction "32_32") (pintype "passive"))
    )
    (net (code "40") (name "/PB3_MISO") (class "Default")
      (node (ref "IC3") (pin "22") (pinfunction "(MISO/PCINT3)PB3_22") (pintype "passive"))
      (node (ref "ICSP") (pin "1") (pinfunction "1_1") (pintype "passive"))
      (node (ref "M1") (pin "7") (pinfunction "DO_7") (pintype "passive"))
      (node (ref "U7A") (pin "15") (pinfunction "MISO_15") (pintype "passive"))
      (node (ref "XIO") (pin "31") (pinfunction "31_31") (pintype "passive"))
    )
    (net (code "41") (name "/PB4") (class "Default")
      (node (ref "IC3") (pin "23") (pinfunction "(OC2A/PCINT4)PB4_23") (pintype "passive"))
      (node (ref "JP1") (pin "8") (pinfunction "8_8") (pintype "passive"))
    )
    (net (code "42") (name "/PB5") (class "Default")
      (node (ref "IC3") (pin "24") (pinfunction "(OC1A/PCINT5)PB5_24") (pintype "passive"))
      (node (ref "JP1") (pin "7") (pinfunction "7_7") (pintype "passive"))
    )
    (net (code "43") (name "/PB6") (class "Default")
      (node (ref "IC3") (pin "25") (pinfunction "(OC1B/PCINT6)PB6_25") (pintype "passive"))
      (node (ref "JP1") (pin "6") (pinfunction "6_6") (pintype "passive"))
    )
    (net (code "44") (name "/PB7") (class "Default")
      (node (ref "IC3") (pin "26") (pinfunction "(OC0A/OC1C/PCINT7)PB7_26") (pintype "passive"))
      (node (ref "JP1") (pin "5") (pinfunction "5_5") (pintype "passive"))
    )
    (net (code "45") (name "/PC0") (class "Default")
      (node (ref "IC3") (pin "53") (pinfunction "(A8)PC0_53") (pintype "passive"))
      (node (ref "XIO") (pin "18") (pinfunction "18_18") (pintype "passive"))
    )
    (net (code "46") (name "/PC1") (class "Default")
      (node (ref "IC3") (pin "54") (pinfunction "(A9)PC1_54") (pintype "passive"))
      (node (ref "XIO") (pin "17") (pinfunction "17_17") (pintype "passive"))
    )
    (net (code "47") (name "/PC2") (class "Default")
      (node (ref "IC3") (pin "55") (pinfunction "(A10)PC2_55") (pintype "passive"))
      (node (ref "XIO") (pin "16") (pinfunction "16_16") (pintype "passive"))
    )
    (net (code "48") (name "/PC3") (class "Default")
      (node (ref "IC3") (pin "56") (pinfunction "(A11)PC3_56") (pintype "passive"))
      (node (ref "XIO") (pin "15") (pinfunction "15_15") (pintype "passive"))
    )
    (net (code "49") (name "/PC4") (class "Default")
      (node (ref "IC3") (pin "57") (pinfunction "(A12)PC4_57") (pintype "passive"))
      (node (ref "XIO") (pin "14") (pinfunction "14_14") (pintype "passive"))
    )
    (net (code "50") (name "/PC5") (class "Default")
      (node (ref "IC3") (pin "58") (pinfunction "(A13)PC5_58") (pintype "passive"))
      (node (ref "XIO") (pin "13") (pinfunction "13_13") (pintype "passive"))
    )
    (net (code "51") (name "/PC6") (class "Default")
      (node (ref "IC3") (pin "59") (pinfunction "(A14)PC6_59") (pintype "passive"))
      (node (ref "XIO") (pin "12") (pinfunction "12_12") (pintype "passive"))
    )
    (net (code "52") (name "/PC7") (class "Default")
      (node (ref "IC3") (pin "60") (pinfunction "(A15)PC7_60") (pintype "passive"))
      (node (ref "XIO") (pin "11") (pinfunction "11_11") (pintype "passive"))
    )
    (net (code "53") (name "/PD7") (class "Default")
      (node (ref "IC3") (pin "50") (pinfunction "(T0)PD7_50") (pintype "passive"))
      (node (ref "XIO") (pin "19") (pinfunction "19_19") (pintype "passive"))
    )
    (net (code "54") (name "/PE0") (class "Default")
      (node (ref "IC3") (pin "2") (pinfunction "(RXD0/PCIN8)PE0_2") (pintype "passive"))
      (node (ref "PWML") (pin "1") (pinfunction "1_1") (pintype "passive"))
    )
    (net (code "55") (name "/PE1") (class "Default")
      (node (ref "IC3") (pin "3") (pinfunction "(TXD0)PE1_3") (pintype "passive"))
      (node (ref "PWML") (pin "2") (pinfunction "2_2") (pintype "passive"))
    )
    (net (code "56") (name "/PE3") (class "Default")
      (node (ref "IC3") (pin "5") (pinfunction "(OC3A/AIN1)PE3_5") (pintype "passive"))
      (node (ref "PWML") (pin "6") (pinfunction "6_6") (pintype "passive"))
    )
    (net (code "57") (name "/PE4") (class "Default")
      (node (ref "IC3") (pin "6") (pinfunction "(OC3B/INT4)PE4_6") (pintype "passive"))
      (node (ref "PWML") (pin "3") (pinfunction "3_3") (pintype "passive"))
    )
    (net (code "58") (name "/PE5") (class "Default")
      (node (ref "IC3") (pin "7") (pinfunction "(OC3C/INT5)PE5_7") (pintype "passive"))
      (node (ref "PWML") (pin "4") (pinfunction "4_4") (pintype "passive"))
    )
    (net (code "59") (name "/PE6") (class "Default")
      (node (ref "IC3") (pin "8") (pinfunction "(T3/INT6)PE6_8") (pintype "passive"))
      (node (ref "J8_b") (pin "2") (pinfunction "2_2") (pintype "passive"))
    )
    (net (code "60") (name "/PG0") (class "Default")
      (node (ref "IC3") (pin "51") (pinfunction "(WR)PG0_51") (pintype "passive"))
      (node (ref "XIO") (pin "22") (pinfunction "22_22") (pintype "passive"))
    )
    (net (code "61") (name "/PG1") (class "Default")
      (node (ref "IC3") (pin "52") (pinfunction "(RD)PG1_52") (pintype "passive"))
      (node (ref "XIO") (pin "21") (pinfunction "21_21") (pintype "passive"))
    )
    (net (code "62") (name "/PG2") (class "Default")
      (node (ref "IC3") (pin "70") (pinfunction "(ALE)PG2_70") (pintype "passive"))
      (node (ref "XIO") (pin "20") (pinfunction "20_20") (pintype "passive"))
    )
    (net (code "63") (name "/PG5") (class "Default")
      (node (ref "IC3") (pin "1") (pinfunction "(OC0B)PG5_1") (pintype "passive"))
      (node (ref "PWML") (pin "5") (pinfunction "5_5") (pintype "passive"))
    )
    (net (code "64") (name "/PH3") (class "Default")
      (node (ref "IC3") (pin "15") (pinfunction "PH3(OC4A)_15") (pintype "passive"))
      (node (ref "PWML") (pin "7") (pinfunction "7_7") (pintype "passive"))
    )
    (net (code "65") (name "/PH4") (class "Default")
      (node (ref "IC3") (pin "16") (pinfunction "PH4(OC4B)_16") (pintype "passive"))
      (node (ref "J6_a") (pin "2") (pinfunction "2_2") (pintype "passive"))
      (node (ref "PWML") (pin "8") (pinfunction "8_8") (pintype "passive"))
    )
    (net (code "66") (name "/PH5") (class "Default")
      (node (ref "IC3") (pin "17") (pinfunction "PH5(OC4C)_17") (pintype "passive"))
      (node (ref "JP1") (pin "10") (pinfunction "10_10") (pintype "passive"))
    )
    (net (code "67") (name "/PH6") (class "Default")
      (node (ref "IC3") (pin "18") (pinfunction "PH6(OC2B)_18") (pintype "passive"))
      (node (ref "JP1") (pin "9") (pinfunction "9_9") (pintype "passive"))
    )
    (net (code "68") (name "/PH7") (class "Default")
      (node (ref "IC3") (pin "27") (pinfunction "PH7(T4)_27") (pintype "passive"))
      (node (ref "J7_b") (pin "2") (pinfunction "2_2") (pintype "passive"))
    )
    (net (code "69") (name "/PJ2") (class "Default")
      (node (ref "IC3") (pin "65") (pinfunction "PJ2(XCK3/PCINT11)_65") (pintype "passive"))
      (node (ref "J6_b") (pin "2") (pinfunction "2_2") (pintype "passive"))
    )
    (net (code "70") (name "/PJ6") (class "Default")
      (node (ref "IC3") (pin "69") (pinfunction "PJ6(PCINT15)_69") (pintype "passive"))
      (node (ref "J8_a") (pin "2") (pinfunction "2_2") (pintype "passive"))
    )
    (net (code "71") (name "/PL0") (class "Default")
      (node (ref "IC3") (pin "35") (pinfunction "PL0(ICP4)_35") (pintype "passive"))
      (node (ref "XIO") (pin "30") (pinfunction "30_30") (pintype "passive"))
    )
    (net (code "72") (name "/PL1") (class "Default")
      (node (ref "IC3") (pin "36") (pinfunction "PL1(ICP5)_36") (pintype "passive"))
      (node (ref "XIO") (pin "29") (pinfunction "29_29") (pintype "passive"))
    )
    (net (code "73") (name "/PL2") (class "Default")
      (node (ref "IC3") (pin "37") (pinfunction "PL2(T5)_37") (pintype "passive"))
      (node (ref "XIO") (pin "28") (pinfunction "28_28") (pintype "passive"))
    )
    (net (code "74") (name "/PL3") (class "Default")
      (node (ref "IC3") (pin "38") (pinfunction "PL3(OC5A)_38") (pintype "passive"))
      (node (ref "XIO") (pin "27") (pinfunction "27_27") (pintype "passive"))
    )
    (net (code "75") (name "/PL4") (class "Default")
      (node (ref "IC3") (pin "39") (pinfunction "PL4(OC5B)_39") (pintype "passive"))
      (node (ref "XIO") (pin "26") (pinfunction "26_26") (pintype "passive"))
    )
    (net (code "76") (name "/PL5") (class "Default")
      (node (ref "IC3") (pin "40") (pinfunction "PL5(OC5C)_40") (pintype "passive"))
      (node (ref "XIO") (pin "25") (pinfunction "25_25") (pintype "passive"))
    )
    (net (code "77") (name "/PL6") (class "Default")
      (node (ref "IC3") (pin "41") (pinfunction "PL6_41") (pintype "passive"))
      (node (ref "XIO") (pin "24") (pinfunction "24_24") (pintype "passive"))
    )
    (net (code "78") (name "/PL7") (class "Default")
      (node (ref "IC3") (pin "42") (pinfunction "PL7_42") (pintype "passive"))
      (node (ref "XIO") (pin "23") (pinfunction "23_23") (pintype "passive"))
    )
    (net (code "79") (name "/PVIN") (class "Default")
      (node (ref "C31") (pin "1") (pinfunction "1_1") (pintype "passive"))
      (node (ref "J4") (pin "2") (pinfunction "2_2") (pintype "passive"))
      (node (ref "J4_a") (pin "1") (pinfunction "1_1") (pintype "passive"))
      (node (ref "U4") (pin "1") (pinfunction "AVIN_1") (pintype "passive"))
      (node (ref "U4") (pin "6") (pinfunction "PVIN_6") (pintype "passive"))
      (node (ref "U4") (pin "7") (pinfunction "PVIN_7") (pintype "passive"))
    )
    (net (code "80") (name "/PWM_3") (class "Default")
      (node (ref "C26") (pin "2") (pinfunction "2_2") (pintype "passive"))
      (node (ref "U3") (pin "1") (pinfunction "Vcc_1") (pintype "power_in"))
      (node (ref "U3") (pin "6") (pinfunction "VS2_6") (pintype "passive"))
      (node (ref "U3") (pin "7") (pinfunction "VS1_7") (pintype "passive"))
      (node (ref "U3") (pin "8") (pinfunction "PWM_8") (pintype "input"))
    )
    (net (code "81") (name "/R") (class "Default")
      (node (ref "D5") (pin "2") (pinfunction "A2_2") (pintype "passive"))
      (node (ref "L-R") (pin "2") (pinfunction "P2_2") (pintype "passive"))
    )
    (net (code "82") (name "/RESET") (class "Default")
      (node (ref "C43") (pin "1") (pinfunction "1_1") (pintype "passive"))
      (node (ref "D7") (pin "A") (pinfunction "A_A") (pintype "passive"))
      (node (ref "IC3") (pin "30") (pinfunction "RESET_30") (pintype "passive"))
      (node (ref "ICSP") (pin "5") (pinfunction "5_5") (pintype "passive"))
      (node (ref "POWER") (pin "3") (pinfunction "3_3") (pintype "passive"))
      (node (ref "RESET") (pin "1") (pinfunction "J1_1") (pintype "passive"))
      (node (ref "RN1") (pin "6") (pinfunction "6_6") (pintype "passive"))
    )
    (net (code "83") (name "/RST_3V3") (class "Default")
      (node (ref "IC5") (pin "4") (pinfunction "Y_4") (pintype "output"))
      (node (ref "U7A") (pin "12") (pinfunction "RES_12") (pintype "passive"))
    )
    (net (code "84") (name "/RST_5V") (class "Default")
      (node (ref "IC5") (pin "2") (pinfunction "A_2") (pintype "input"))
      (node (ref "J6_a") (pin "1") (pinfunction "1_1") (pintype "passive"))
      (node (ref "J6_b") (pin "1") (pinfunction "1_1") (pintype "passive"))
      (node (ref "RN6") (pin "1") (pinfunction "1_1") (pintype "passive"))
    )
    (net (code "85") (name "/RXD1") (class "Default")
      (node (ref "COMMUNICATION") (pin "3") (pinfunction "3_3") (pintype "passive"))
      (node (ref "IC3") (pin "45") (pinfunction "(RXD1/INT2)PD2_45") (pintype "passive"))
    )
    (net (code "86") (name "/RXD2") (class "Default")
      (node (ref "COMMUNICATION") (pin "5") (pinfunction "5_5") (pintype "passive"))
      (node (ref "IC3") (pin "12") (pinfunction "PH0(RXD2)_12") (pintype "passive"))
    )
    (net (code "87") (name "/RXD3") (class "Default")
      (node (ref "COMMUNICATION") (pin "7") (pinfunction "7_7") (pintype "passive"))
      (node (ref "IC3") (pin "63") (pinfunction "PJ0(RXD3/PCINT9)_63") (pintype "passive"))
    )
    (net (code "88") (name "/SCK_3V3") (class "Default")
      (node (ref "IC6") (pin "4") (pinfunction "Y_4") (pintype "output"))
      (node (ref "U7A") (pin "13") (pinfunction "SCK_13") (pintype "passive"))
    )
    (net (code "89") (name "/SCL") (class "Default")
      (node (ref "COMMUNICATION") (pin "1") (pinfunction "1_1") (pintype "passive"))
      (node (ref "IC3") (pin "43") (pinfunction "(SCL/INT0)PD0_43") (pintype "passive"))
      (node (ref "JP1") (pin "1") (pinfunction "1_1") (pintype "passive"))
      (node (ref "RN1") (pin "2") (pinfunction "2_2") (pintype "passive"))
    )
    (net (code "90") (name "/SDA") (class "Default")
      (node (ref "COMMUNICATION") (pin "2") (pinfunction "2_2") (pintype "passive"))
      (node (ref "IC3") (pin "44") (pinfunction "(SDA/INT1)PD1_44") (pintype "passive"))
      (node (ref "JP1") (pin "2") (pinfunction "2_2") (pintype "passive"))
      (node (ref "RN1") (pin "4") (pinfunction "4_4") (pintype "passive"))
    )
    (net (code "91") (name "/SS_3V3") (class "Default")
      (node (ref "IC8") (pin "4") (pinfunction "Y_4") (pintype "output"))
      (node (ref "U7A") (pin "14") (pinfunction "SS_14") (pintype "passive"))
    )
    (net (code "92") (name "/SS_MAX5") (class "Default")
      (node (ref "IC8") (pin "2") (pinfunction "A_2") (pintype "input"))
      (node (ref "J7_a") (pin "1") (pinfunction "1_1") (pintype "passive"))
      (node (ref "J7_b") (pin "1") (pinfunction "1_1") (pintype "passive"))
      (node (ref "RN6") (pin "8") (pinfunction "8_8") (pintype "passive"))
    )
    (net (code "93") (name "/TOP") (class "Default")
      (node (ref "D1") (pin "1") (pinfunction "A1_1") (pintype "passive"))
      (node (ref "T-B") (pin "3") (pinfunction "P3_3") (pintype "passive"))
    )
    (net (code "94") (name "/TXD1") (class "Default")
      (node (ref "COMMUNICATION") (pin "4") (pinfunction "4_4") (pintype "passive"))
      (node (ref "IC3") (pin "46") (pinfunction "(TXD1/INT3)PD3_46") (pintype "passive"))
    )
    (net (code "95") (name "/TXD2") (class "Default")
      (node (ref "COMMUNICATION") (pin "6") (pinfunction "6_6") (pintype "passive"))
      (node (ref "IC3") (pin "13") (pinfunction "PH1(TXD2)_13") (pintype "passive"))
    )
    (net (code "96") (name "/TXD3") (class "Default")
      (node (ref "COMMUNICATION") (pin "8") (pinfunction "8_8") (pintype "passive"))
      (node (ref "IC3") (pin "64") (pinfunction "PJ1(TXD3/PCINT10)_64") (pintype "passive"))
    )
    (net (code "97") (name "/USBVCC") (class "Default")
      (node (ref "D2") (pin "K") (pinfunction "K_K") (pintype "passive"))
      (node (ref "D4") (pin "K") (pinfunction "K_K") (pintype "passive"))
      (node (ref "D6") (pin "K") (pinfunction "K_K") (pintype "passive"))
      (node (ref "F2") (pin "2") (pinfunction "2_2") (pintype "passive"))
      (node (ref "USB") (pin "1") (pinfunction "P1_1") (pintype "passive"))
    )
    (net (code "98") (name "/VCC_1") (class "Default")
      (node (ref "C6") (pin "2") (pinfunction "2_2") (pintype "passive"))
      (node (ref "U1") (pin "1") (pinfunction "Vcc_1") (pintype "power_in"))
      (node (ref "U1") (pin "6") (pinfunction "VS2_6") (pintype "passive"))
      (node (ref "U1") (pin "7") (pinfunction "VS1_7") (pintype "passive"))
      (node (ref "U1") (pin "8") (pinfunction "PWM_8") (pintype "input"))
    )
    (net (code "99") (name "/VCC_2") (class "Default")
      (node (ref "C16") (pin "2") (pinfunction "2_2") (pintype "passive"))
      (node (ref "U2") (pin "1") (pinfunction "Vcc_1") (pintype "power_in"))
      (node (ref "U2") (pin "6") (pinfunction "VS2_6") (pintype "passive"))
      (node (ref "U2") (pin "7") (pinfunction "VS1_7") (pintype "passive"))
      (node (ref "U2") (pin "8") (pinfunction "PWM_8") (pintype "input"))
    )
    (net (code "100") (name "/V_bat") (class "Default")
      (node (ref "J4") (pin "1") (pinfunction "1_1") (pintype "passive"))
      (node (ref "J5") (pin "1") (pinfunction "1_1") (pintype "passive"))
      (node (ref "V_BAT") (pin "2") (pinfunction "P2_2") (pintype "passive"))
      (node (ref "V_BAT") (pin "3") (pinfunction "P3_3") (pintype "passive"))
    )
    (net (code "101") (name "/Vin_1") (class "Default")
      (node (ref "C1") (pin "2") (pinfunction "2_2") (pintype "passive"))
      (node (ref "D1") (pin "3") (pinfunction "K_3") (pintype "passive"))
      (node (ref "J1_a") (pin "2") (pinfunction "2_2") (pintype "passive"))
      (node (ref "R1") (pin "2") (pinfunction "2_2") (pintype "passive"))
      (node (ref "U1") (pin "16") (pinfunction "Vin_16") (pintype "power_in"))
    )
    (net (code "102") (name "/Vin_2") (class "Default")
      (node (ref "C11") (pin "2") (pinfunction "2_2") (pintype "passive"))
      (node (ref "D3") (pin "3") (pinfunction "K_3") (pintype "passive"))
      (node (ref "J2_a") (pin "2") (pinfunction "2_2") (pintype "passive"))
      (node (ref "R5") (pin "2") (pinfunction "2_2") (pintype "passive"))
      (node (ref "U2") (pin "16") (pinfunction "Vin_16") (pintype "power_in"))
    )
    (net (code "103") (name "/Vin_3") (class "Default")
      (node (ref "C21") (pin "2") (pinfunction "2_2") (pintype "passive"))
      (node (ref "D5") (pin "3") (pinfunction "K_3") (pintype "passive"))
      (node (ref "J3_a") (pin "2") (pinfunction "2_2") (pintype "passive"))
      (node (ref "R9") (pin "2") (pinfunction "2_2") (pintype "passive"))
      (node (ref "U3") (pin "16") (pinfunction "Vin_16") (pintype "power_in"))
    )
    (net (code "104") (name "/Vout_1") (class "Default")
      (node (ref "D2") (pin "A") (pinfunction "A_A") (pintype "passive"))
      (node (ref "J1_OUT") (pin "2") (pinfunction "2_2") (pintype "passive"))
    )
    (net (code "105") (name "/Vout_2") (class "Default")
      (node (ref "D4") (pin "A") (pinfunction "A_A") (pintype "passive"))
      (node (ref "J2_OUT") (pin "2") (pinfunction "2_2") (pintype "passive"))
    )
    (net (code "106") (name "/Vout_3") (class "Default")
      (node (ref "D6") (pin "A") (pinfunction "A_A") (pintype "passive"))
      (node (ref "J3_OUT") (pin "2") (pinfunction "2_2") (pintype "passive"))
    )
    (net (code "107") (name "/XTAL1") (class "Default")
      (node (ref "IC3") (pin "34") (pinfunction "XTAL1_34") (pintype "passive"))
      (node (ref "Y1") (pin "2") (pinfunction "2_2") (pintype "passive"))
    )
    (net (code "108") (name "/XTAL2") (class "Default")
      (node (ref "IC3") (pin "33") (pinfunction "XTAL2_33") (pintype "output"))
      (node (ref "Y1") (pin "1") (pinfunction "1_1") (pintype "passive"))
    )
    (net (code "109") (name "3V3") (class "Default")
      (node (ref "C48") (pin "1") (pinfunction "1_1") (pintype "passive"))
      (node (ref "C49") (pin "1") (pinfunction "1_1") (pintype "passive"))
      (node (ref "C50") (pin "1") (pinfunction "1_1") (pintype "passive"))
      (node (ref "C50_B") (pin "1") (pinfunction "1_1") (pintype "passive"))
      (node (ref "C55") (pin "2") (pinfunction "2_2") (pintype "passive"))
      (node (ref "C57") (pin "1") (pinfunction "1_1") (pintype "passive"))
      (node (ref "C58") (pin "1") (pinfunction "1_1") (pintype "passive"))
      (node (ref "IC5") (pin "5") (pinfunction "VCC_5") (pintype "passive"))
      (node (ref "IC6") (pin "5") (pinfunction "VCC_5") (pintype "passive"))
      (node (ref "IC8") (pin "5") (pinfunction "VCC_5") (pintype "passive"))
      (node (ref "IC9") (pin "5") (pinfunction "VCC_5") (pintype "passive"))
      (node (ref "J4_OUT") (pin "2") (pinfunction "2_2") (pintype "passive"))
      (node (ref "M1") (pin "4") (pinfunction "VCC_4") (pintype "passive"))
      (node (ref "POWER") (pin "4") (pinfunction "4_4") (pintype "passive"))
      (node (ref "RN6") (pin "3") (pinfunction "3_3") (pintype "passive"))
      (node (ref "U7A") (pin "2") (pinfunction "VL_2") (pintype "passive"))
      (node (ref "U7A") (pin "23") (pinfunction "VCC_23") (pintype "passive"))
    )
    (net (code "110") (name "5V") (class "Default")
      (node (ref "C45") (pin "1") (pinfunction "1_1") (pintype "passive"))
      (node (ref "C46") (pin "1") (pinfunction "1_1") (pintype "passive"))
      (node (ref "C47") (pin "1") (pinfunction "1_1") (pintype "passive"))
      (node (ref "C60") (pin "1") (pinfunction "1_1") (pintype "passive"))
      (node (ref "C61") (pin "1") (pinfunction "1_1") (pintype "passive"))
      (node (ref "D7") (pin "K") (pinfunction "K_K") (pintype "passive"))
      (node (ref "IC3") (pin "10") (pinfunction "VCC_10") (pintype "power_in"))
      (node (ref "IC3") (pin "100") (pinfunction "AVCC_100") (pintype "power_in"))
      (node (ref "IC3") (pin "31") (pinfunction "VCC1_31") (pintype "power_in"))
      (node (ref "IC3") (pin "61") (pinfunction "VCC2_61") (pintype "power_in"))
      (node (ref "IC3") (pin "80") (pinfunction "VCC3_80") (pintype "power_in"))
      (node (ref "ICSP") (pin "2") (pinfunction "2_2") (pintype "passive"))
      (node (ref "J5_OUT") (pin "2") (pinfunction "2_2") (pintype "passive"))
      (node (ref "L7") (pin "1") (pinfunction "1_1") (pintype "passive"))
      (node (ref "POWER") (pin "2") (pinfunction "2_2") (pintype "passive"))
      (node (ref "POWER") (pin "5") (pinfunction "5_5") (pintype "passive"))
      (node (ref "RN1") (pin "1") (pinfunction "1_1") (pintype "passive"))
      (node (ref "RN1") (pin "3") (pinfunction "3_3") (pintype "passive"))
      (node (ref "RN1") (pin "5") (pinfunction "5_5") (pintype "passive"))
      (node (ref "RN6") (pin "7") (pinfunction "7_7") (pintype "passive"))
      (node (ref "XIO") (pin "1") (pinfunction "1_1") (pintype "passive"))
      (node (ref "XIO") (pin "2") (pinfunction "2_2") (pintype "passive"))
    )
    (net (code "111") (name "GND") (class "Default")
      (node (ref "C1") (pin "1") (pinfunction "1_1") (pintype "passive"))
      (node (ref "C11") (pin "1") (pinfunction "1_1") (pintype "passive"))
      (node (ref "C12") (pin "1") (pinfunction "1_1") (pintype "passive"))
      (node (ref "C16") (pin "1") (pinfunction "1_1") (pintype "passive"))
      (node (ref "C2") (pin "1") (pinfunction "1_1") (pintype "passive"))
      (node (ref "C21") (pin "1") (pinfunction "1_1") (pintype "passive"))
      (node (ref "C22") (pin "1") (pinfunction "1_1") (pintype "passive"))
      (node (ref "C26") (pin "1") (pinfunction "1_1") (pintype "passive"))
      (node (ref "C31") (pin "2") (pinfunction "2_2") (pintype "passive"))
      (node (ref "C32") (pin "1") (pinfunction "1_1") (pintype "passive"))
      (node (ref "C33") (pin "2") (pinfunction "2_2") (pintype "passive"))
      (node (ref "C34") (pin "1") (pinfunction "1_1") (pintype "passive"))
      (node (ref "C37") (pin "1") (pinfunction "1_1") (pintype "passive"))
      (node (ref "C38") (pin "1") (pinfunction "1_1") (pintype "passive"))
      (node (ref "C42") (pin "2") (pinfunction "2_2") (pintype "passive"))
      (node (ref "C43") (pin "2") (pinfunction "2_2") (pintype "passive"))
      (node (ref "C44") (pin "2") (pinfunction "2_2") (pintype "passive"))
      (node (ref "C45") (pin "2") (pinfunction "2_2") (pintype "passive"))
      (node (ref "C46") (pin "2") (pinfunction "2_2") (pintype "passive"))
      (node (ref "C47") (pin "2") (pinfunction "2_2") (pintype "passive"))
      (node (ref "C48") (pin "2") (pinfunction "2_2") (pintype "passive"))
      (node (ref "C49") (pin "2") (pinfunction "2_2") (pintype "passive"))
      (node (ref "C50") (pin "2") (pinfunction "2_2") (pintype "passive"))
      (node (ref "C50_B") (pin "2") (pinfunction "2_2") (pintype "passive"))
      (node (ref "C51") (pin "2") (pinfunction "2_2") (pintype "passive"))
      (node (ref "C52") (pin "1") (pinfunction "1_1") (pintype "passive"))
      (node (ref "C53") (pin "1") (pinfunction "1_1") (pintype "passive"))
      (node (ref "C54") (pin "2") (pinfunction "2_2") (pintype "passive"))
      (node (ref "C55") (pin "1") (pinfunction "1_1") (pintype "passive"))
      (node (ref "C57") (pin "2") (pinfunction "2_2") (pintype "passive"))
      (node (ref "C58") (pin "2") (pinfunction "2_2") (pintype "passive"))
      (node (ref "C6") (pin "1") (pinfunction "1_1") (pintype "passive"))
      (node (ref "C60") (pin "2") (pinfunction "2_2") (pintype "passive"))
      (node (ref "C61") (pin "2") (pinfunction "2_2") (pintype "passive"))
      (node (ref "F-B") (pin "1") (pinfunction "P1_1") (pintype "passive"))
      (node (ref "F-B") (pin "4") (pinfunction "P4_4") (pintype "passive"))
      (node (ref "IC3") (pin "11") (pinfunction "GND_11") (pintype "power_in"))
      (node (ref "IC3") (pin "32") (pinfunction "GND1_32") (pintype "power_in"))
      (node (ref "IC3") (pin "62") (pinfunction "GND2_62") (pintype "power_in"))
      (node (ref "IC3") (pin "81") (pinfunction "GND3_81") (pintype "power_in"))
      (node (ref "IC3") (pin "99") (pinfunction "AGND_99") (pintype "power_in"))
      (node (ref "IC5") (pin "1") (pinfunction "~{OE}_1") (pintype "input"))
      (node (ref "IC5") (pin "3") (pinfunction "GND_3") (pintype "passive"))
      (node (ref "IC6") (pin "1") (pinfunction "~{OE}_1") (pintype "input"))
      (node (ref "IC6") (pin "3") (pinfunction "GND_3") (pintype "passive"))
      (node (ref "IC8") (pin "1") (pinfunction "~{OE}_1") (pintype "input"))
      (node (ref "IC8") (pin "3") (pinfunction "GND_3") (pintype "passive"))
      (node (ref "IC9") (pin "1") (pinfunction "~{OE}_1") (pintype "input"))
      (node (ref "IC9") (pin "3") (pinfunction "GND_3") (pintype "passive"))
      (node (ref "ICSP") (pin "6") (pinfunction "6_6") (pintype "passive"))
      (node (ref "JP1") (pin "4") (pinfunction "4_4") (pintype "passive"))
      (node (ref "L-R") (pin "1") (pinfunction "P1_1") (pintype "passive"))
      (node (ref "L-R") (pin "4") (pinfunction "P4_4") (pintype "passive"))
      (node (ref "M1") (pin "10") (pinfunction "SHIELD_10") (pintype "passive"))
      (node (ref "M1") (pin "11") (pinfunction "SHIELD_11") (pintype "passive"))
      (node (ref "M1") (pin "12") (pinfunction "SHIELD_12") (pintype "passive"))
      (node (ref "M1") (pin "6") (pinfunction "GND_6") (pintype "passive"))
      (node (ref "M1") (pin "9") (pinfunction "SHIELD_9") (pintype "passive"))
      (node (ref "POWER") (pin "6") (pinfunction "6_6") (pintype "passive"))
      (node (ref "POWER") (pin "7") (pinfunction "7_7") (pintype "passive"))
      (node (ref "R10") (pin "1") (pinfunction "1_1") (pintype "passive"))
      (node (ref "R13") (pin "1") (pinfunction "1_1") (pintype "passive"))
      (node (ref "R17") (pin "1") (pinfunction "1_1") (pintype "passive"))
      (node (ref "R2") (pin "1") (pinfunction "1_1") (pintype "passive"))
      (node (ref "R6") (pin "1") (pinfunction "1_1") (pintype "passive"))
      (node (ref "RESET") (pin "2") (pinfunction "J2_2") (pintype "passive"))
      (node (ref "RN6") (pin "2") (pinfunction "2_2") (pintype "passive"))
      (node (ref "T-B") (pin "1") (pinfunction "P1_1") (pintype "passive"))
      (node (ref "T-B") (pin "4") (pinfunction "P4_4") (pintype "passive"))
      (node (ref "U1") (pin "13") (pinfunction "PGND_13") (pintype "power_in"))
      (node (ref "U1") (pin "17") (pinfunction "PGND_17") (pintype "power_in"))
      (node (ref "U1") (pin "4") (pinfunction "GND_4") (pintype "power_in"))
      (node (ref "U1") (pin "5") (pinfunction "VS3_5") (pintype "passive"))
      (node (ref "U2") (pin "13") (pinfunction "PGND_13") (pintype "power_in"))
      (node (ref "U2") (pin "17") (pinfunction "PGND_17") (pintype "power_in"))
      (node (ref "U2") (pin "4") (pinfunction "GND_4") (pintype "power_in"))
      (node (ref "U2") (pin "5") (pinfunction "VS3_5") (pintype "passive"))
      (node (ref "U3") (pin "13") (pinfunction "PGND_13") (pintype "power_in"))
      (node (ref "U3") (pin "17") (pinfunction "PGND_17") (pintype "power_in"))
      (node (ref "U3") (pin "4") (pinfunction "GND_4") (pintype "power_in"))
      (node (ref "U3") (pin "5") (pinfunction "VS3_5") (pintype "passive"))
      (node (ref "U4") (pin "10") (pinfunction "PGND_10") (pintype "passive"))
      (node (ref "U4") (pin "11") (pinfunction "PGND_11") (pintype "passive"))
      (node (ref "U4") (pin "3") (pinfunction "SGND_3") (pintype "passive"))
      (node (ref "U5") (pin "1") (pinfunction "GND_1") (pintype "passive"))
      (node (ref "U5") (pin "10") (pinfunction "GND_10") (pintype "passive"))
      (node (ref "U5") (pin "11") (pinfunction "GND_11") (pintype "passive"))
      (node (ref "U5") (pin "20") (pinfunction "GND_20") (pintype "passive"))
      (node (ref "U5") (pin "4") (pinfunction "OVP_4") (pintype "input"))
      (node (ref "U7A") (pin "19") (pinfunction "GND_19") (pintype "passive"))
      (node (ref "U7A") (pin "3") (pinfunction "GND_3") (pintype "passive"))
      (node (ref "USB") (pin "4") (pinfunction "P4_4") (pintype "passive"))
      (node (ref "V_BAT") (pin "1") (pinfunction "P1_1") (pintype "passive"))
      (node (ref "V_BAT") (pin "4") (pinfunction "P4_4") (pintype "passive"))
      (node (ref "XIO") (pin "35") (pinfunction "35_35") (pintype "passive"))
      (node (ref "XIO") (pin "36") (pinfunction "36_36") (pintype "passive"))
      (node (ref "Y1") (pin "3") (pinfunction "3_3") (pintype "passive"))
      (node (ref "Y3") (pin "2") (pinfunction "GND_2") (pintype "passive"))
      (node (ref "Y3") (pin "4") (pinfunction "GND_4") (pintype "passive"))
    )
    (net (code "112") (name "Net-(C34-Pad2)") (class "Default")
      (node (ref "C34") (pin "2") (pinfunction "2_2") (pintype "passive"))
      (node (ref "J5") (pin "2") (pinfunction "2_2") (pintype "passive"))
      (node (ref "J5_a") (pin "2") (pinfunction "2_2") (pintype "passive"))
      (node (ref "U5") (pin "5") (pinfunction "V_IN_5") (pintype "passive"))
      (node (ref "U5") (pin "6") (pinfunction "V_IN_6") (pintype "passive"))
    )
    (net (code "113") (name "Net-(C35-Pad1)") (class "Default")
      (node (ref "C35") (pin "1") (pinfunction "1_1") (pintype "passive"))
      (node (ref "L5") (pin "1") (pinfunction "1_1") (pintype "passive"))
      (node (ref "U5") (pin "15") (pinfunction "SW1_15") (pintype "passive"))
      (node (ref "U5") (pin "16") (pinfunction "SW1_16") (pintype "passive"))
    )
    (net (code "114") (name "Net-(C36-Pad1)") (class "Default")
      (node (ref "C36") (pin "1") (pinfunction "1_1") (pintype "passive"))
      (node (ref "L5") (pin "2") (pinfunction "2_2") (pintype "passive"))
      (node (ref "U5") (pin "12") (pinfunction "SW2_12") (pintype "passive"))
      (node (ref "U5") (pin "13") (pinfunction "SW2_13") (pintype "passive"))
    )
    (net (code "115") (name "Net-(C40-Pad2)") (class "Default")
      (node (ref "C40") (pin "2") (pinfunction "2_2") (pintype "passive"))
      (node (ref "R14") (pin "2") (pinfunction "2_2") (pintype "passive"))
    )
    (net (code "116") (name "Net-(C41-Pad2)") (class "Default")
      (node (ref "C41") (pin "2") (pinfunction "2_2") (pintype "passive"))
      (node (ref "R16") (pin "2") (pinfunction "2_2") (pintype "passive"))
    )
    (net (code "117") (name "Net-(C51-Pad1)") (class "Default")
      (node (ref "C51") (pin "1") (pinfunction "1_1") (pintype "passive"))
      (node (ref "F2") (pin "1") (pinfunction "1_1") (pintype "passive"))
      (node (ref "L7") (pin "2") (pinfunction "2_2") (pintype "passive"))
    )
    (net (code "118") (name "Net-(L4-Pad1)") (class "Default")
      (node (ref "L4") (pin "1") (pinfunction "1_1") (pintype "passive"))
      (node (ref "U4") (pin "8") (pinfunction "SW_8") (pintype "passive"))
      (node (ref "U4") (pin "9") (pinfunction "SW_9") (pintype "passive"))
    )
    (net (code "119") (name "Net-(U1-BST1)") (class "Default")
      (node (ref "C4") (pin "1") (pinfunction "1_1") (pintype "passive"))
      (node (ref "U1") (pin "15") (pinfunction "BST1_15") (pintype "power_in"))
    )
    (net (code "120") (name "Net-(U1-BST2)") (class "Default")
      (node (ref "C5") (pin "1") (pinfunction "1_1") (pintype "passive"))
      (node (ref "U1") (pin "11") (pinfunction "BST2_11") (pintype "power_in"))
    )
    (net (code "121") (name "Net-(U1-MPPC)") (class "Default")
      (node (ref "R1") (pin "1") (pinfunction "1_1") (pintype "passive"))
      (node (ref "R2") (pin "2") (pinfunction "2_2") (pintype "passive"))
      (node (ref "U1") (pin "3") (pinfunction "MPPC_3") (pintype "input"))
    )
    (net (code "122") (name "Net-(U1-RUN)") (class "Default")
      (node (ref "J1_a") (pin "1") (pinfunction "1_1") (pintype "passive"))
      (node (ref "U1") (pin "2") (pinfunction "RUN_2") (pintype "input"))
    )
    (net (code "123") (name "Net-(U1-SW1)") (class "Default")
      (node (ref "C4") (pin "2") (pinfunction "2_2") (pintype "passive"))
      (node (ref "L1") (pin "1") (pinfunction "1_1") (pintype "passive"))
      (node (ref "U1") (pin "14") (pinfunction "SW1_14") (pintype "power_in"))
    )
    (net (code "124") (name "Net-(U1-SW2)") (class "Default")
      (node (ref "C5") (pin "2") (pinfunction "2_2") (pintype "passive"))
      (node (ref "L1") (pin "2") (pinfunction "2_2") (pintype "passive"))
      (node (ref "U1") (pin "12") (pinfunction "SW2_12") (pintype "power_in"))
    )
    (net (code "125") (name "Net-(U1-Vout)") (class "Default")
      (node (ref "C2") (pin "2") (pinfunction "2_2") (pintype "passive"))
      (node (ref "J1_OUT") (pin "1") (pinfunction "1_1") (pintype "passive"))
      (node (ref "U1") (pin "10") (pinfunction "Vout_10") (pintype "power_in"))
    )
    (net (code "126") (name "Net-(U2-BST1)") (class "Default")
      (node (ref "C14") (pin "1") (pinfunction "1_1") (pintype "passive"))
      (node (ref "U2") (pin "15") (pinfunction "BST1_15") (pintype "power_in"))
    )
    (net (code "127") (name "Net-(U2-BST2)") (class "Default")
      (node (ref "C15") (pin "1") (pinfunction "1_1") (pintype "passive"))
      (node (ref "U2") (pin "11") (pinfunction "BST2_11") (pintype "power_in"))
    )
    (net (code "128") (name "Net-(U2-MPPC)") (class "Default")
      (node (ref "R5") (pin "1") (pinfunction "1_1") (pintype "passive"))
      (node (ref "R6") (pin "2") (pinfunction "2_2") (pintype "passive"))
      (node (ref "U2") (pin "3") (pinfunction "MPPC_3") (pintype "input"))
    )
    (net (code "129") (name "Net-(U2-RUN)") (class "Default")
      (node (ref "J2_a") (pin "1") (pinfunction "1_1") (pintype "passive"))
      (node (ref "U2") (pin "2") (pinfunction "RUN_2") (pintype "input"))
    )
    (net (code "130") (name "Net-(U2-SW1)") (class "Default")
      (node (ref "C14") (pin "2") (pinfunction "2_2") (pintype "passive"))
      (node (ref "L2") (pin "1") (pinfunction "1_1") (pintype "passive"))
      (node (ref "U2") (pin "14") (pinfunction "SW1_14") (pintype "power_in"))
    )
    (net (code "131") (name "Net-(U2-SW2)") (class "Default")
      (node (ref "C15") (pin "2") (pinfunction "2_2") (pintype "passive"))
      (node (ref "L2") (pin "2") (pinfunction "2_2") (pintype "passive"))
      (node (ref "U2") (pin "12") (pinfunction "SW2_12") (pintype "power_in"))
    )
    (net (code "132") (name "Net-(U2-Vout)") (class "Default")
      (node (ref "C12") (pin "2") (pinfunction "2_2") (pintype "passive"))
      (node (ref "J2_OUT") (pin "1") (pinfunction "1_1") (pintype "passive"))
      (node (ref "U2") (pin "10") (pinfunction "Vout_10") (pintype "power_in"))
    )
    (net (code "133") (name "Net-(U3-BST1)") (class "Default")
      (node (ref "C24") (pin "1") (pinfunction "1_1") (pintype "passive"))
      (node (ref "U3") (pin "15") (pinfunction "BST1_15") (pintype "power_in"))
    )
    (net (code "134") (name "Net-(U3-BST2)") (class "Default")
      (node (ref "C25") (pin "1") (pinfunction "1_1") (pintype "passive"))
      (node (ref "U3") (pin "11") (pinfunction "BST2_11") (pintype "power_in"))
    )
    (net (code "135") (name "Net-(U3-MPPC)") (class "Default")
      (node (ref "R10") (pin "2") (pinfunction "2_2") (pintype "passive"))
      (node (ref "R9") (pin "1") (pinfunction "1_1") (pintype "passive"))
      (node (ref "U3") (pin "3") (pinfunction "MPPC_3") (pintype "input"))
    )
    (net (code "136") (name "Net-(U3-RUN)") (class "Default")
      (node (ref "J3_a") (pin "1") (pinfunction "1_1") (pintype "passive"))
      (node (ref "U3") (pin "2") (pinfunction "RUN_2") (pintype "input"))
    )
    (net (code "137") (name "Net-(U3-SW1)") (class "Default")
      (node (ref "C24") (pin "2") (pinfunction "2_2") (pintype "passive"))
      (node (ref "L3") (pin "1") (pinfunction "1_1") (pintype "passive"))
      (node (ref "U3") (pin "14") (pinfunction "SW1_14") (pintype "power_in"))
    )
    (net (code "138") (name "Net-(U3-SW2)") (class "Default")
      (node (ref "C25") (pin "2") (pinfunction "2_2") (pintype "passive"))
      (node (ref "L3") (pin "2") (pinfunction "2_2") (pintype "passive"))
      (node (ref "U3") (pin "12") (pinfunction "SW2_12") (pintype "power_in"))
    )
    (net (code "139") (name "Net-(U3-Vout)") (class "Default")
      (node (ref "C22") (pin "2") (pinfunction "2_2") (pintype "passive"))
      (node (ref "J3_OUT") (pin "1") (pinfunction "1_1") (pintype "passive"))
      (node (ref "U3") (pin "10") (pinfunction "Vout_10") (pintype "power_in"))
    )
    (net (code "140") (name "Net-(U4-EN)") (class "Default")
      (node (ref "J4_a") (pin "2") (pinfunction "2_2") (pintype "passive"))
      (node (ref "U4") (pin "2") (pinfunction "EN_2") (pintype "passive"))
    )
    (net (code "141") (name "Net-(U4-SS)") (class "Default")
      (node (ref "C32") (pin "2") (pinfunction "2_2") (pintype "passive"))
      (node (ref "U4") (pin "4") (pinfunction "SS_4") (pintype "passive"))
    )
    (net (code "142") (name "Net-(U5-BST1)") (class "Default")
      (node (ref "C35") (pin "2") (pinfunction "2_2") (pintype "passive"))
      (node (ref "U5") (pin "17") (pinfunction "BST1_17") (pintype "passive"))
    )
    (net (code "143") (name "Net-(U5-BST2)") (class "Default")
      (node (ref "C36") (pin "2") (pinfunction "2_2") (pintype "passive"))
      (node (ref "U5") (pin "14") (pinfunction "BST2_14") (pintype "passive"))
    )
    (net (code "144") (name "Net-(U5-COMP)") (class "Default")
      (node (ref "C39") (pin "2") (pinfunction "2_2") (pintype "passive"))
      (node (ref "C40") (pin "1") (pinfunction "1_1") (pintype "passive"))
      (node (ref "U5") (pin "2") (pinfunction "COMP_2") (pintype "passive"))
    )
    (net (code "145") (name "Net-(U5-FB)") (class "Default")
      (node (ref "C39") (pin "1") (pinfunction "1_1") (pintype "passive"))
      (node (ref "R14") (pin "1") (pinfunction "1_1") (pintype "passive"))
      (node (ref "R15") (pin "1") (pinfunction "1_1") (pintype "passive"))
      (node (ref "R16") (pin "1") (pinfunction "1_1") (pintype "passive"))
      (node (ref "R17") (pin "2") (pinfunction "2_2") (pintype "passive"))
      (node (ref "U5") (pin "3") (pinfunction "FB_3") (pintype "input"))
    )
    (net (code "146") (name "Net-(U5-I_OUT)") (class "Default")
      (node (ref "C38") (pin "2") (pinfunction "2_2") (pintype "passive"))
      (node (ref "R13") (pin "2") (pinfunction "2_2") (pintype "passive"))
      (node (ref "U5") (pin "8") (pinfunction "I_OUT_8") (pintype "output"))
    )
    (net (code "147") (name "Net-(U5-PWM{slash}SYNC)") (class "Default")
      (node (ref "C37") (pin "2") (pinfunction "2_2") (pintype "passive"))
      (node (ref "U5") (pin "18") (pinfunction "VCC_18") (pintype "passive"))
      (node (ref "U5") (pin "19") (pinfunction "PWM/SYNC_19") (pintype "input"))
    )
    (net (code "148") (name "Net-(U5-RUN)") (class "Default")
      (node (ref "J5_a") (pin "1") (pinfunction "1_1") (pintype "passive"))
      (node (ref "U5") (pin "7") (pinfunction "RUN_7") (pintype "input"))
    )
    (net (code "149") (name "Net-(U5-V_OUT)") (class "Default")
      (node (ref "C41") (pin "1") (pinfunction "1_1") (pintype "passive"))
      (node (ref "C42") (pin "1") (pinfunction "1_1") (pintype "passive"))
      (node (ref "J5_OUT") (pin "1") (pinfunction "1_1") (pintype "passive"))
      (node (ref "R15") (pin "2") (pinfunction "2_2") (pintype "passive"))
      (node (ref "U5") (pin "9") (pinfunction "V_OUT_9") (pintype "passive"))
    )
    (net (code "150") (name "Net-(U7A-D+)") (class "Default")
      (node (ref "RN7") (pin "4") (pinfunction "4_4") (pintype "passive"))
      (node (ref "U7A") (pin "21") (pinfunction "D+_21") (pintype "passive"))
    )
    (net (code "151") (name "Net-(U7A-D-)") (class "Default")
      (node (ref "RN7") (pin "2") (pinfunction "2_2") (pintype "passive"))
      (node (ref "U7A") (pin "20") (pinfunction "D-_20") (pintype "passive"))
    )
    (net (code "152") (name "Net-(U7A-VBCOMP)") (class "Default")
      (node (ref "C54") (pin "1") (pinfunction "1_1") (pintype "passive"))
      (node (ref "U7A") (pin "22") (pinfunction "VBCOMP_22") (pintype "passive"))
    )
    (net (code "153") (name "Net-(U7A-XI)") (class "Default")
      (node (ref "C53") (pin "2") (pinfunction "2_2") (pintype "passive"))
      (node (ref "U7A") (pin "24") (pinfunction "XI_24") (pintype "passive"))
      (node (ref "Y3") (pin "3") (pinfunction "X2_3") (pintype "passive"))
    )
    (net (code "154") (name "Net-(U7A-XO)") (class "Default")
      (node (ref "C52") (pin "2") (pinfunction "2_2") (pintype "passive"))
      (node (ref "U7A") (pin "25") (pinfunction "XO_25") (pintype "passive"))
      (node (ref "Y3") (pin "1") (pinfunction "X1_1") (pintype "passive"))
    )
    (net (code "155") (name "unconnected-(IC3-(CLKO{slash}ICP3{slash}INT7)PE7-Pad9)") (class "Default")
      (node (ref "IC3") (pin "9") (pinfunction "(CLKO/ICP3/INT7)PE7_9") (pintype "passive"))
    )
    (net (code "156") (name "unconnected-(IC3-(ICP1)PD4-Pad47)") (class "Default")
      (node (ref "IC3") (pin "47") (pinfunction "(ICP1)PD4_47") (pintype "passive"))
    )
    (net (code "157") (name "unconnected-(IC3-(T1)PD6-Pad49)") (class "Default")
      (node (ref "IC3") (pin "49") (pinfunction "(T1)PD6_49") (pintype "passive"))
    )
    (net (code "158") (name "unconnected-(IC3-(TOSC1)PG4-Pad29)") (class "Default")
      (node (ref "IC3") (pin "29") (pinfunction "(TOSC1)PG4_29") (pintype "passive"))
    )
    (net (code "159") (name "unconnected-(IC3-(TOSC2)PG3-Pad28)") (class "Default")
      (node (ref "IC3") (pin "28") (pinfunction "(TOSC2)PG3_28") (pintype "passive"))
    )
    (net (code "160") (name "unconnected-(IC3-(XCK0{slash}AIN0)PE2-Pad4)") (class "Default")
      (node (ref "IC3") (pin "4") (pinfunction "(XCK0/AIN0)PE2_4") (pintype "passive"))
    )
    (net (code "161") (name "unconnected-(IC3-(XCK1)PD5-Pad48)") (class "Default")
      (node (ref "IC3") (pin "48") (pinfunction "(XCK1)PD5_48") (pintype "passive"))
    )
    (net (code "162") (name "unconnected-(IC3-PH2(XCK2)-Pad14)") (class "Default")
      (node (ref "IC3") (pin "14") (pinfunction "PH2(XCK2)_14") (pintype "passive"))
    )
    (net (code "163") (name "unconnected-(IC3-PJ4(PCINT13)-Pad67)") (class "Default")
      (node (ref "IC3") (pin "67") (pinfunction "PJ4(PCINT13)_67") (pintype "passive"))
    )
    (net (code "164") (name "unconnected-(IC3-PJ5(PCINT14)-Pad68)") (class "Default")
      (node (ref "IC3") (pin "68") (pinfunction "PJ5(PCINT14)_68") (pintype "passive"))
    )
    (net (code "165") (name "unconnected-(IC3-PJ7-Pad79)") (class "Default")
      (node (ref "IC3") (pin "79") (pinfunction "PJ7_79") (pintype "passive"))
    )
    (net (code "166") (name "unconnected-(M1-NC-Pad1)") (class "Default")
      (node (ref "M1") (pin "1") (pinfunction "NC_1") (pintype "passive"))
    )
    (net (code "167") (name "unconnected-(M1-RSV-Pad8)") (class "Default")
      (node (ref "M1") (pin "8") (pinfunction "RSV_8") (pintype "passive"))
    )
    (net (code "168") (name "unconnected-(POWER-Pad1)") (class "Default")
      (node (ref "POWER") (pin "1") (pinfunction "1_1") (pintype "passive"))
    )
    (net (code "169") (name "unconnected-(POWER-Pad8)") (class "Default")
      (node (ref "POWER") (pin "8") (pinfunction "8_8") (pintype "passive"))
    )
    (net (code "170") (name "unconnected-(RN1-Pad7)") (class "Default")
      (node (ref "RN1") (pin "7") (pinfunction "7_7") (pintype "passive"))
    )
    (net (code "171") (name "unconnected-(RN1-Pad8)") (class "Default")
      (node (ref "RN1") (pin "8") (pinfunction "8_8") (pintype "passive"))
    )
    (net (code "172") (name "unconnected-(RN6-Pad5)") (class "Default")
      (node (ref "RN6") (pin "5") (pinfunction "5_5") (pintype "passive"))
    )
    (net (code "173") (name "unconnected-(RN6-Pad6)") (class "Default")
      (node (ref "RN6") (pin "6") (pinfunction "6_6") (pintype "passive"))
    )
    (net (code "174") (name "unconnected-(RN7-Pad1)") (class "Default")
      (node (ref "RN7") (pin "1") (pinfunction "1_1") (pintype "passive"))
    )
    (net (code "175") (name "unconnected-(RN7-Pad6)") (class "Default")
      (node (ref "RN7") (pin "6") (pinfunction "6_6") (pintype "passive"))
    )
    (net (code "176") (name "unconnected-(RN7-Pad7)") (class "Default")
      (node (ref "RN7") (pin "7") (pinfunction "7_7") (pintype "passive"))
    )
    (net (code "177") (name "unconnected-(RN7-Pad8)") (class "Default")
      (node (ref "RN7") (pin "8") (pinfunction "8_8") (pintype "passive"))
    )
    (net (code "178") (name "unconnected-(U1-PGOOD-Pad9)") (class "Default")
      (node (ref "U1") (pin "9") (pinfunction "PGOOD_9") (pintype "passive"))
    )
    (net (code "179") (name "unconnected-(U2-PGOOD-Pad9)") (class "Default")
      (node (ref "U2") (pin "9") (pinfunction "PGOOD_9") (pintype "passive"))
    )
    (net (code "180") (name "unconnected-(U3-PGOOD-Pad9)") (class "Default")
      (node (ref "U3") (pin "9") (pinfunction "PGOOD_9") (pintype "passive"))
    )
    (net (code "181") (name "unconnected-(U4-NC-Pad5)") (class "Default")
      (node (ref "U4") (pin "5") (pinfunction "NC_5") (pintype "passive"))
    )
    (net (code "182") (name "unconnected-(U4-NC-Pad12)") (class "Default")
      (node (ref "U4") (pin "12") (pinfunction "NC_12") (pintype "passive"))
    )
    (net (code "183") (name "unconnected-(U4-NC-Pad13)") (class "Default")
      (node (ref "U4") (pin "13") (pinfunction "NC_13") (pintype "passive"))
    )
    (net (code "184") (name "unconnected-(U7A-GPIN0-Pad26)") (class "Default")
      (node (ref "U7A") (pin "26") (pinfunction "GPIN0_26") (pintype "passive"))
    )
    (net (code "185") (name "unconnected-(U7A-GPIN1-Pad27)") (class "Default")
      (node (ref "U7A") (pin "27") (pinfunction "GPIN1_27") (pintype "passive"))
    )
    (net (code "186") (name "unconnected-(U7A-GPIN2-Pad28)") (class "Default")
      (node (ref "U7A") (pin "28") (pinfunction "GPIN2_28") (pintype "passive"))
    )
    (net (code "187") (name "unconnected-(U7A-GPIN3-Pad29)") (class "Default")
      (node (ref "U7A") (pin "29") (pinfunction "GPIN3_29") (pintype "passive"))
    )
    (net (code "188") (name "unconnected-(U7A-GPIN4-Pad30)") (class "Default")
      (node (ref "U7A") (pin "30") (pinfunction "GPIN4_30") (pintype "passive"))
    )
    (net (code "189") (name "unconnected-(U7A-GPIN5-Pad31)") (class "Default")
      (node (ref "U7A") (pin "31") (pinfunction "GPIN5_31") (pintype "passive"))
    )
    (net (code "190") (name "unconnected-(U7A-GPIN6-Pad32)") (class "Default")
      (node (ref "U7A") (pin "32") (pinfunction "GPIN6_32") (pintype "passive"))
    )
    (net (code "191") (name "unconnected-(U7A-GPIN7-Pad1)") (class "Default")
      (node (ref "U7A") (pin "1") (pinfunction "GPIN7_1") (pintype "passive"))
    )
    (net (code "192") (name "unconnected-(U7A-GPOUT0-Pad4)") (class "Default")
      (node (ref "U7A") (pin "4") (pinfunction "GPOUT0_4") (pintype "passive"))
    )
    (net (code "193") (name "unconnected-(U7A-GPOUT1-Pad5)") (class "Default")
      (node (ref "U7A") (pin "5") (pinfunction "GPOUT1_5") (pintype "passive"))
    )
    (net (code "194") (name "unconnected-(U7A-GPOUT2-Pad6)") (class "Default")
      (node (ref "U7A") (pin "6") (pinfunction "GPOUT2_6") (pintype "passive"))
    )
    (net (code "195") (name "unconnected-(U7A-GPOUT3-Pad7)") (class "Default")
      (node (ref "U7A") (pin "7") (pinfunction "GPOUT3_7") (pintype "passive"))
    )
    (net (code "196") (name "unconnected-(U7A-GPOUT4-Pad8)") (class "Default")
      (node (ref "U7A") (pin "8") (pinfunction "GPOUT4_8") (pintype "passive"))
    )
    (net (code "197") (name "unconnected-(U7A-GPOUT5-Pad9)") (class "Default")
      (node (ref "U7A") (pin "9") (pinfunction "GPOUT5_9") (pintype "passive"))
    )
    (net (code "198") (name "unconnected-(U7A-GPOUT6-Pad10)") (class "Default")
      (node (ref "U7A") (pin "10") (pinfunction "GPOUT6_10") (pintype "passive"))
    )
    (net (code "199") (name "unconnected-(U7A-GPOUT7-Pad11)") (class "Default")
      (node (ref "U7A") (pin "11") (pinfunction "GPOUT7_11") (pintype "passive"))
    )
  )
)
